# PX4mNode_V0_1_1.net
KiCad netlist of a schematic drawn in EAGLE
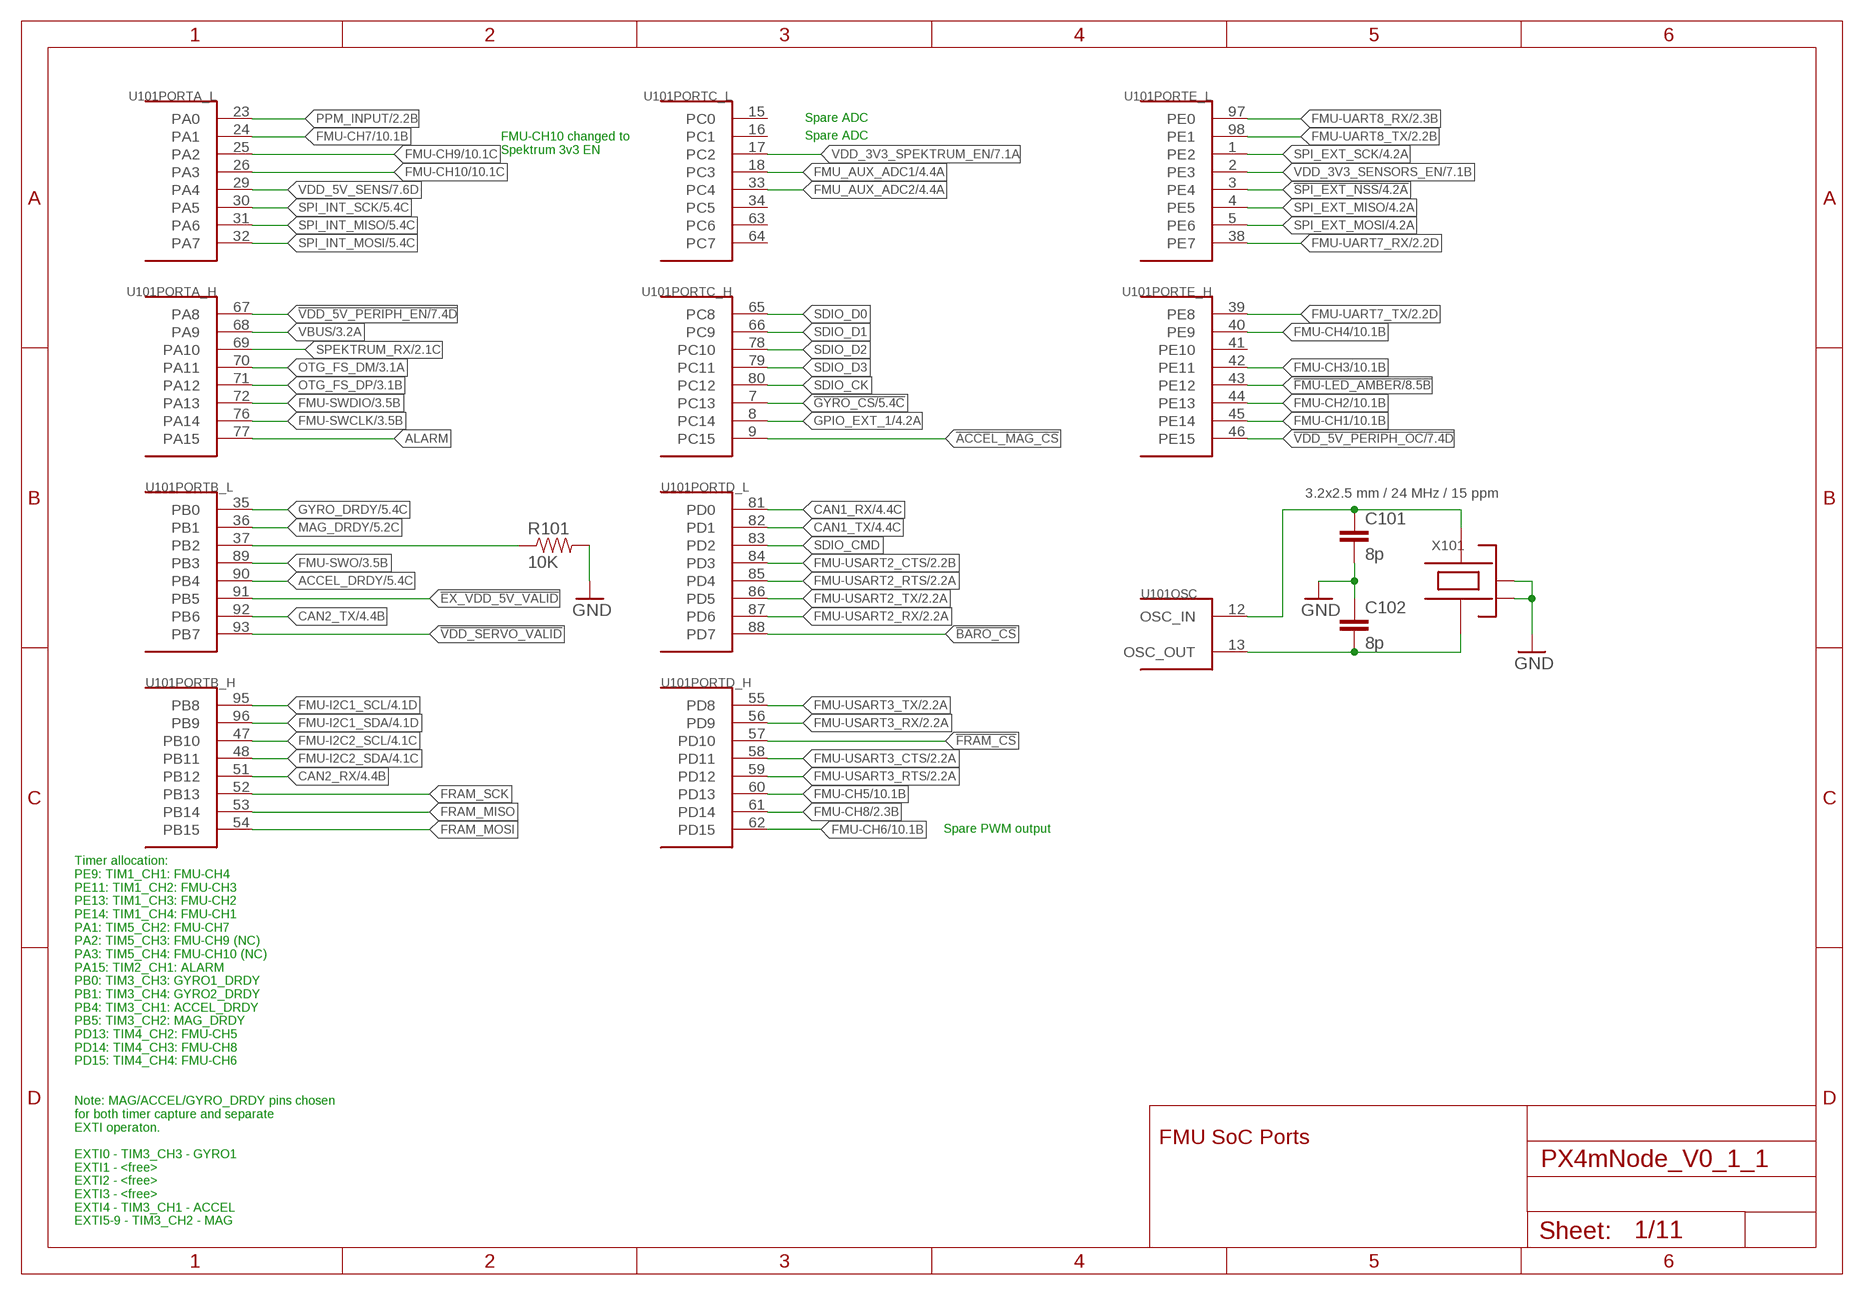
[diagram p0: schematic, sheet 1]
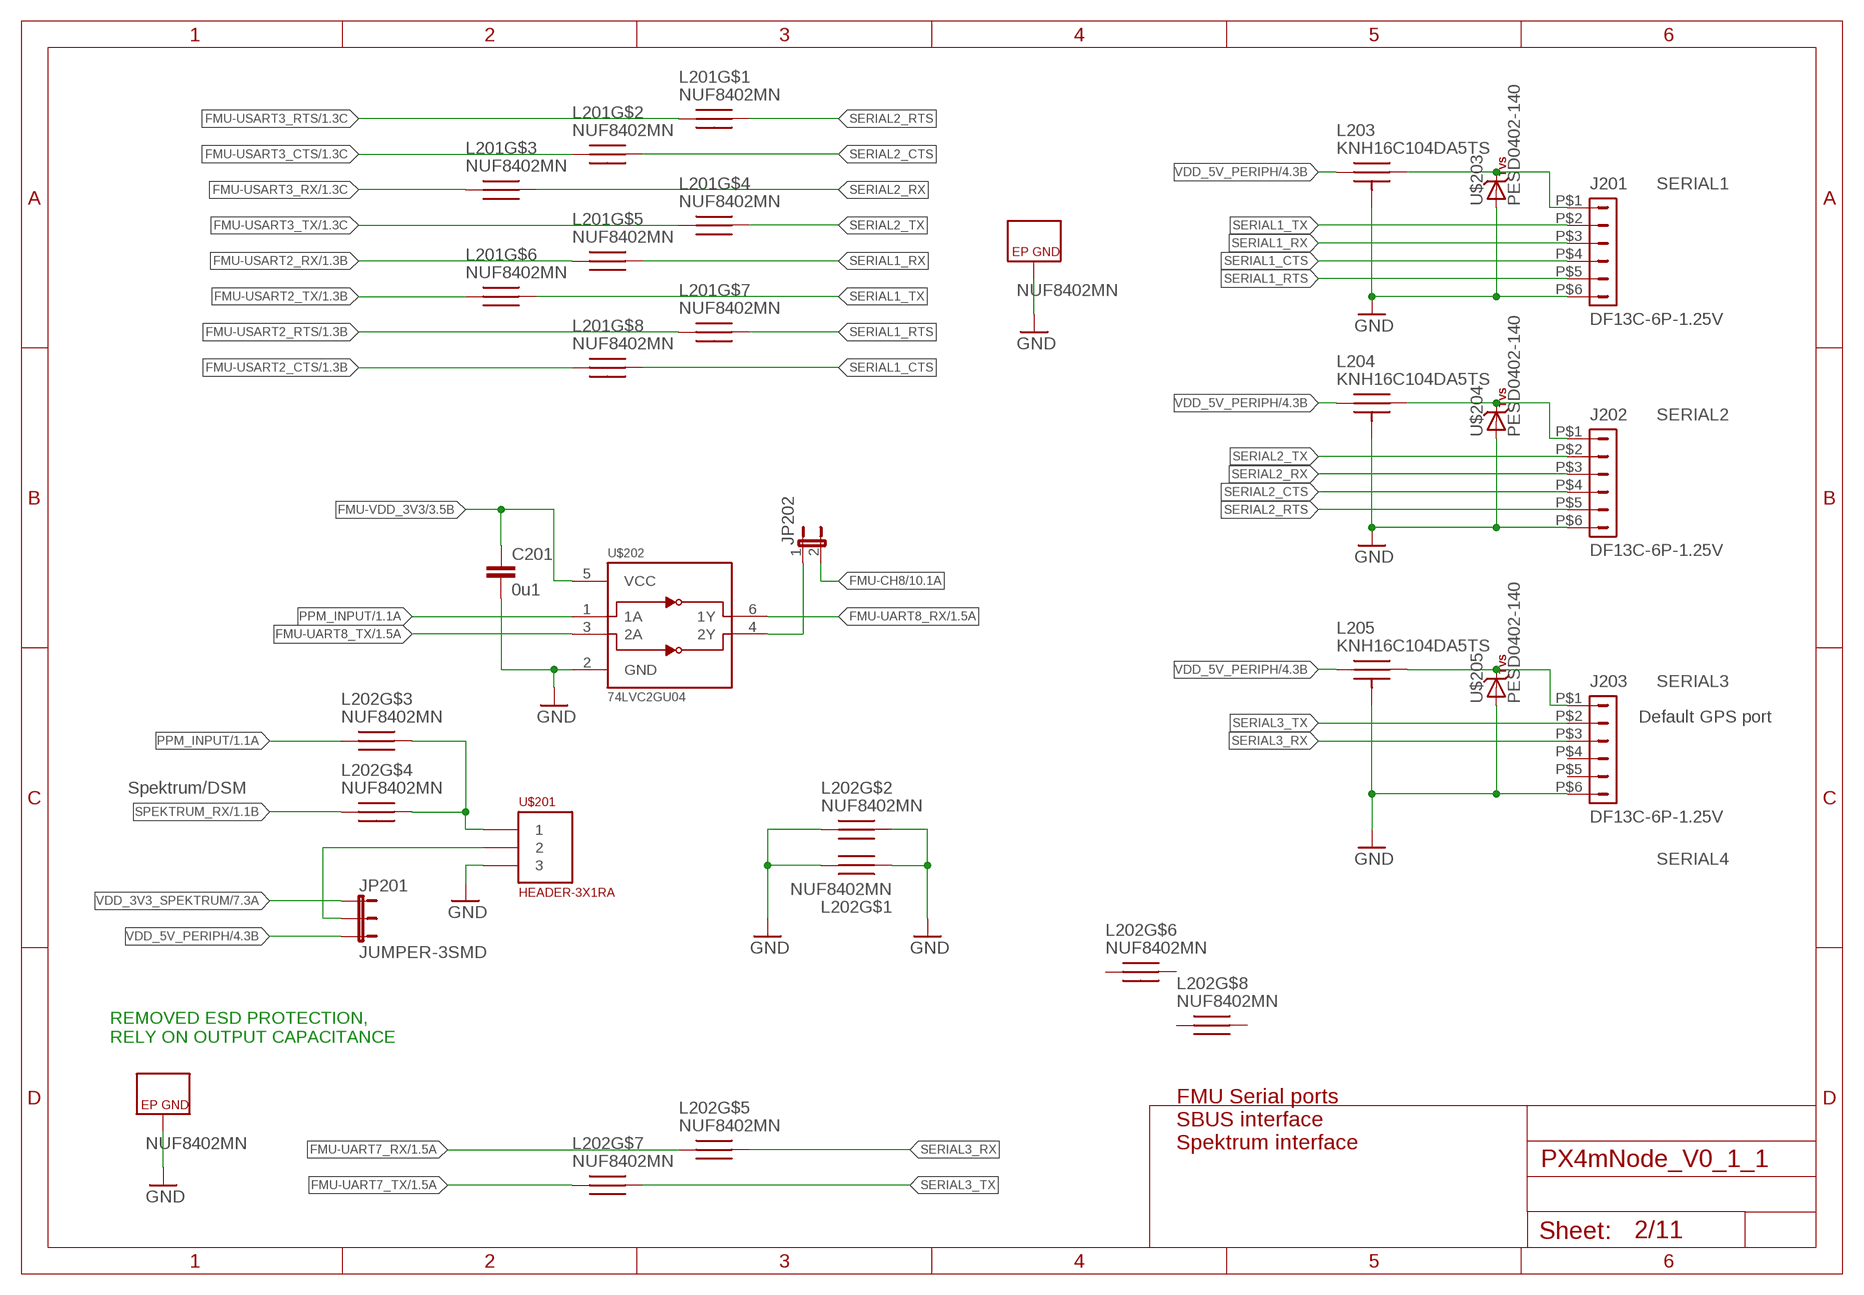
[diagram p1: schematic, sheet 2]
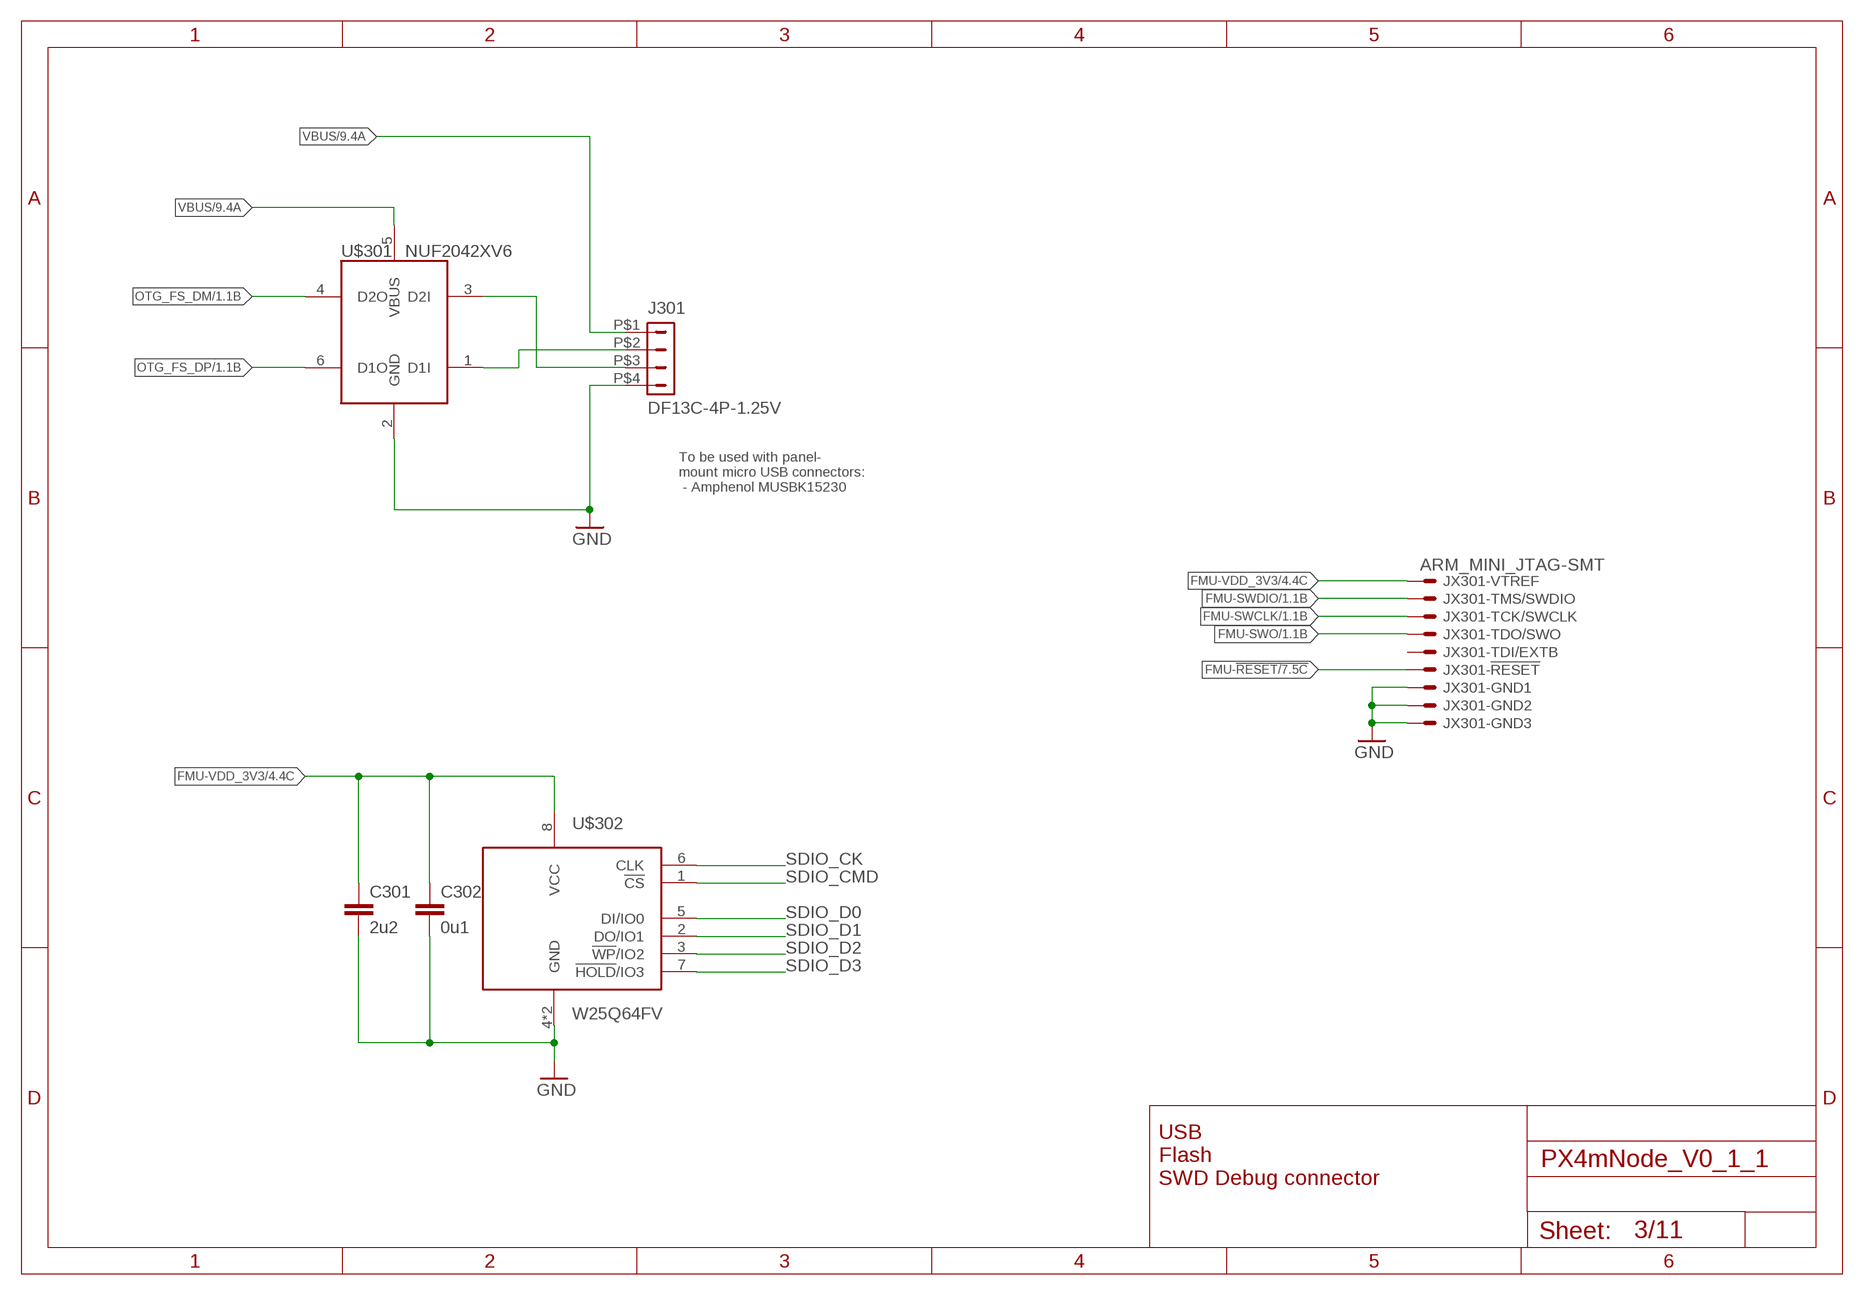
[diagram p2: schematic, sheet 3]
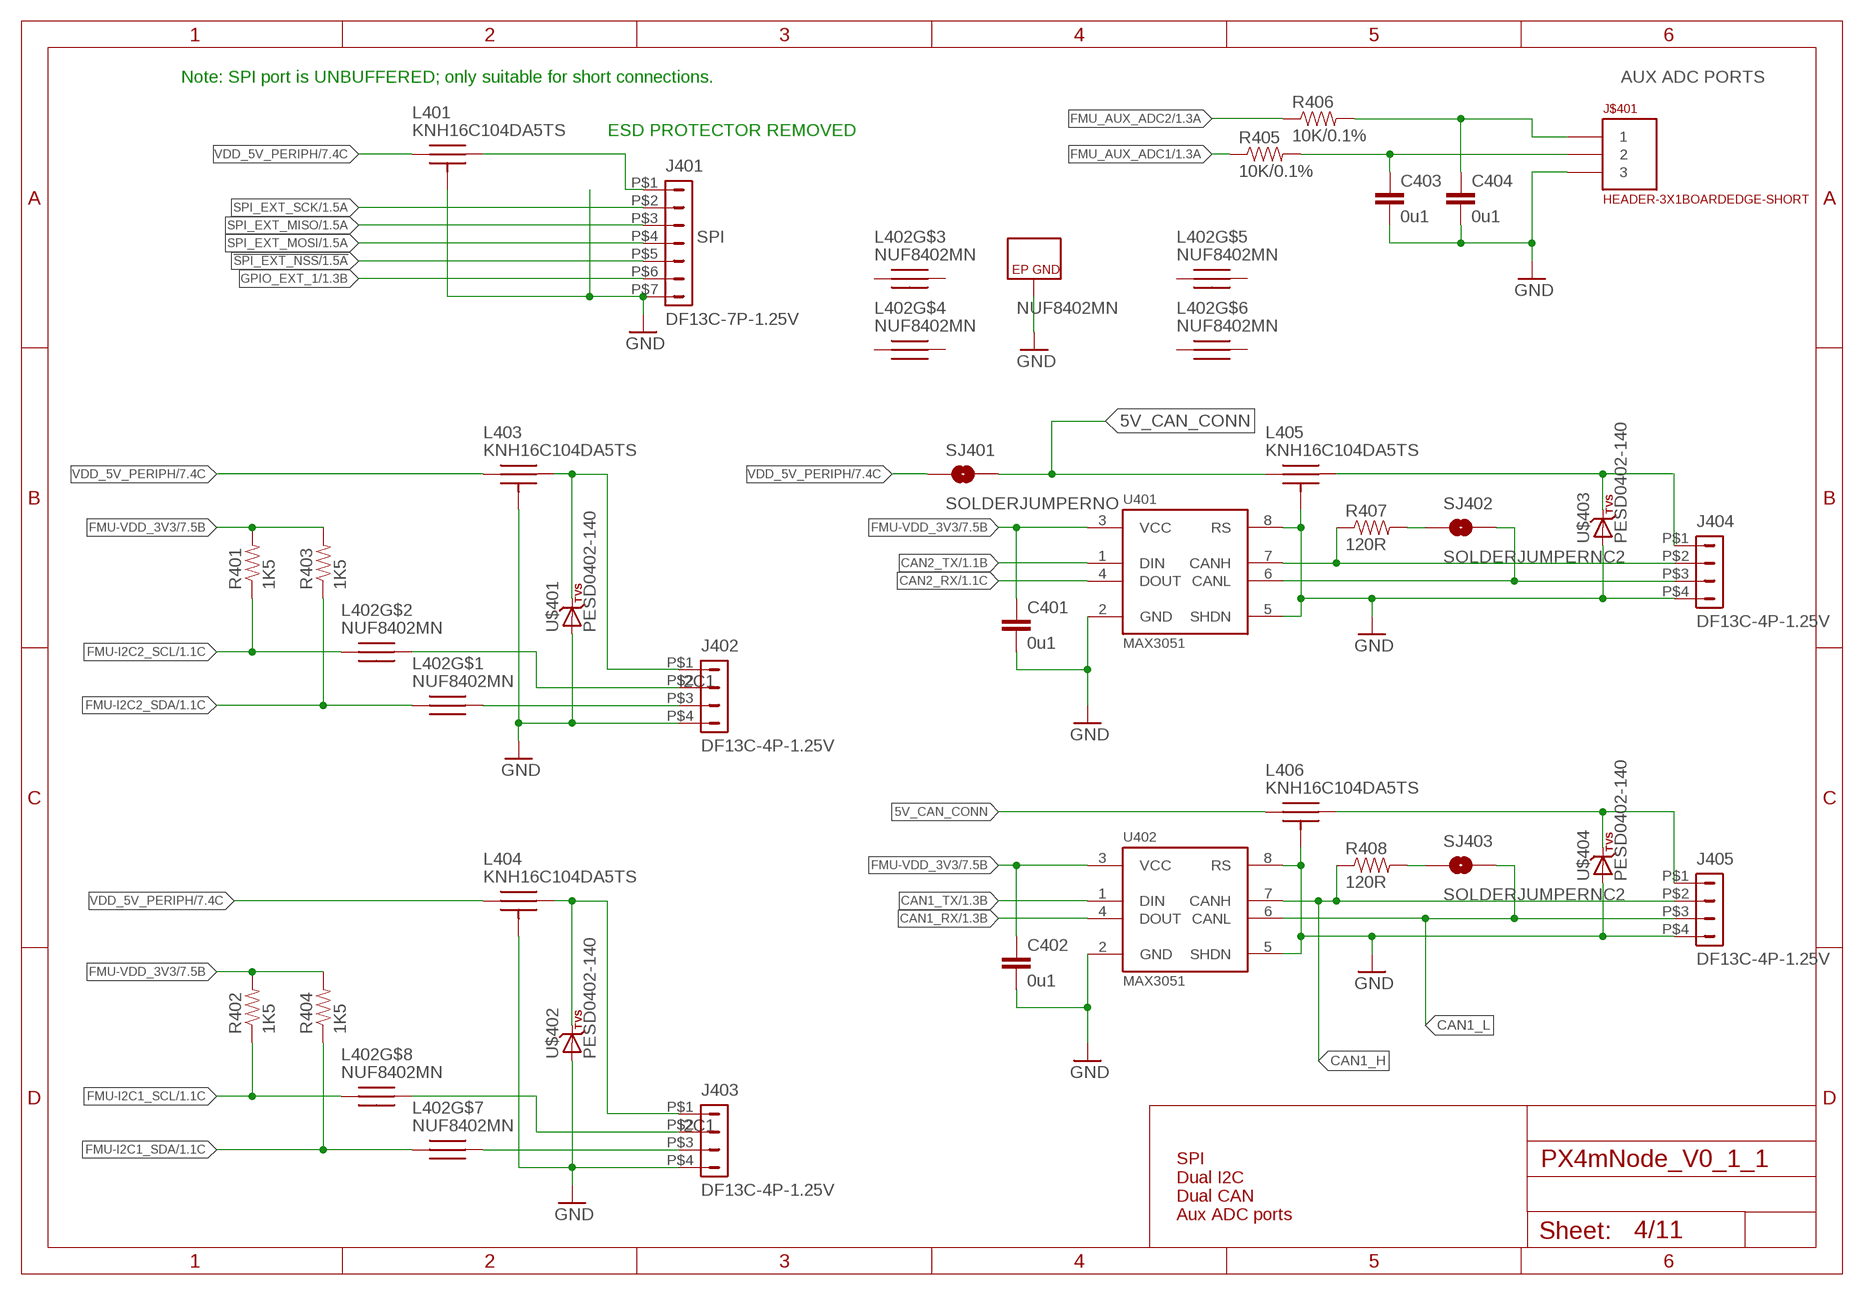
[diagram p3: schematic, sheet 4]
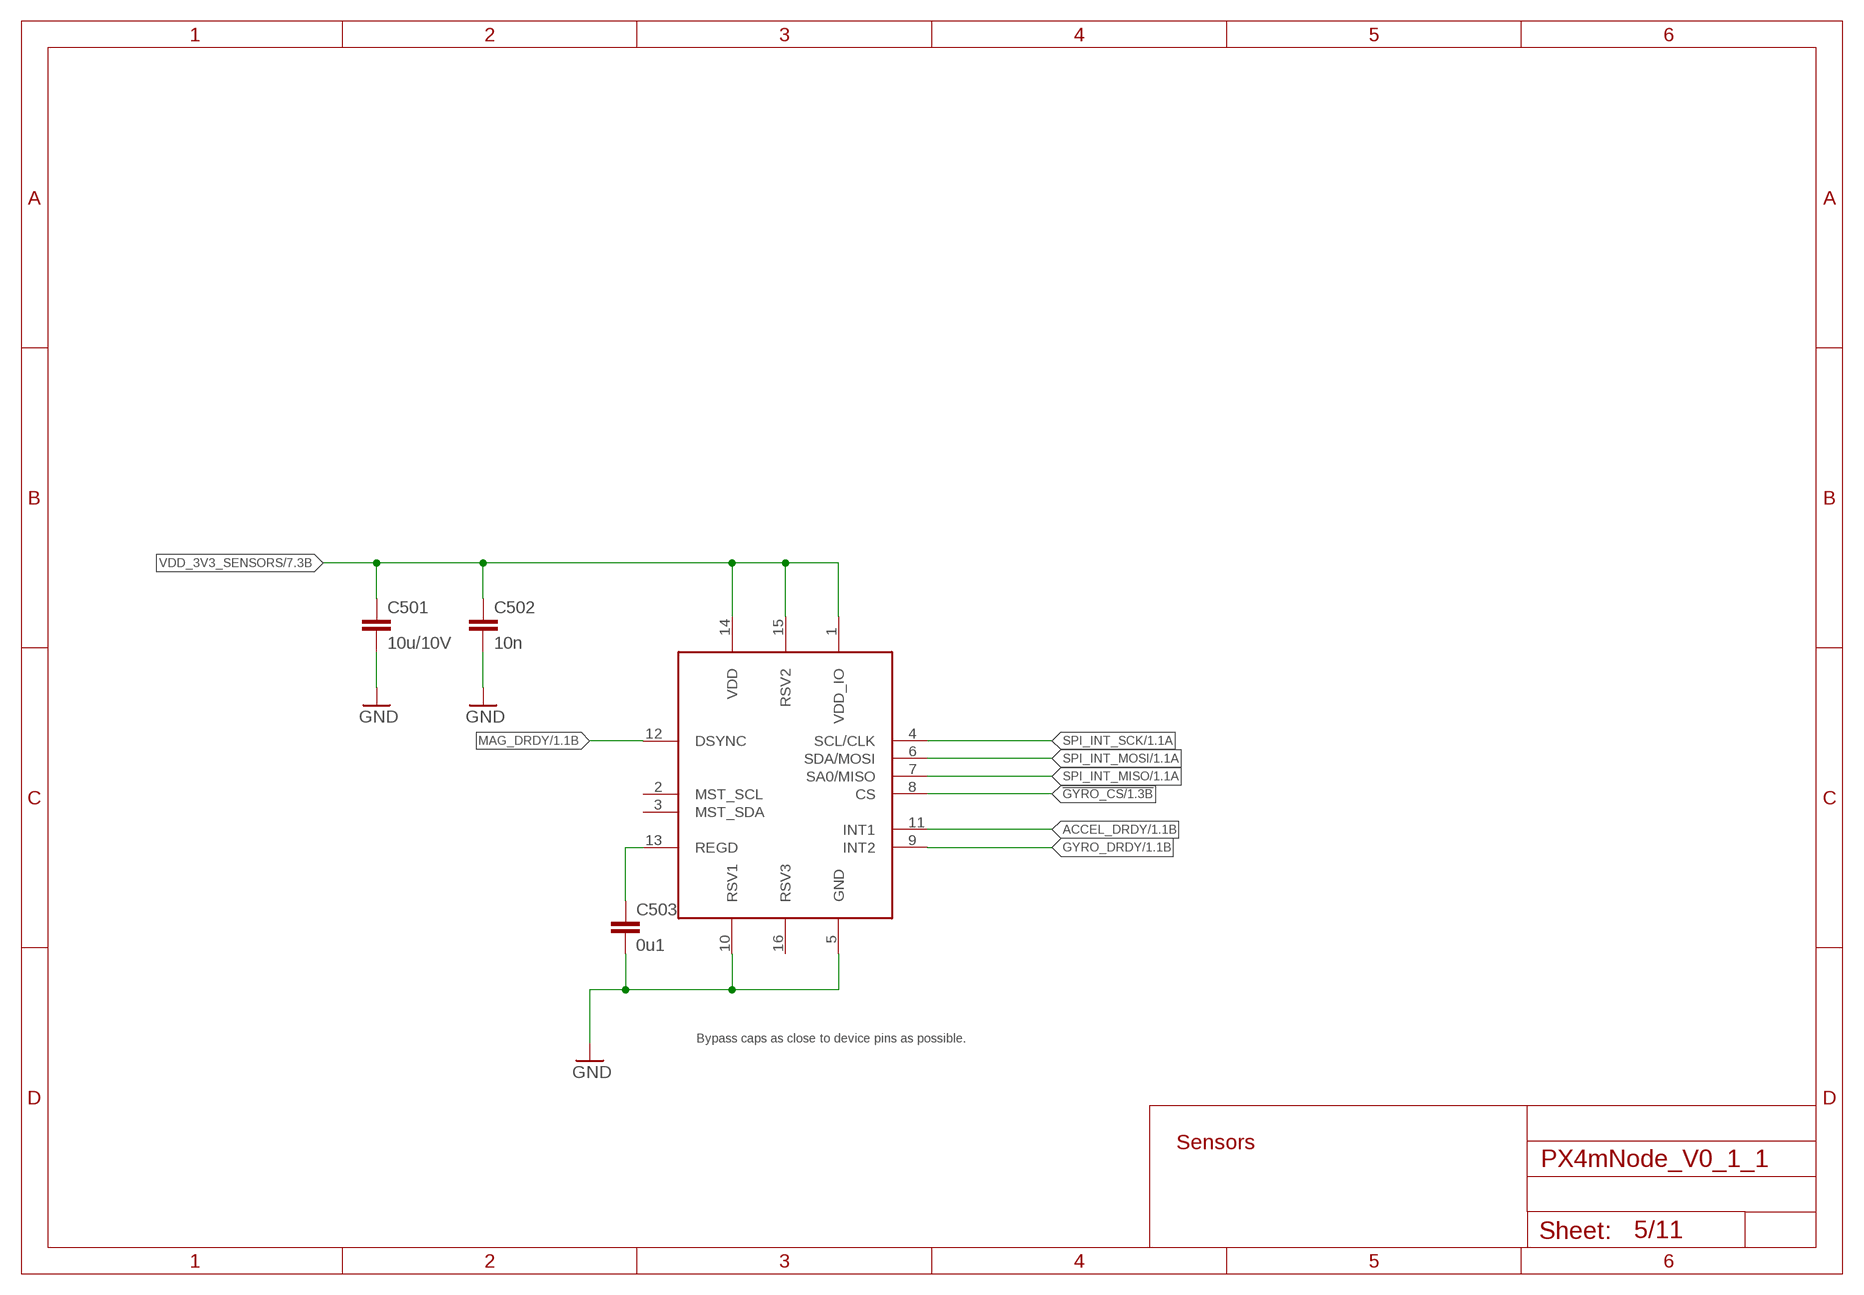
[diagram p4: schematic, sheet 5]
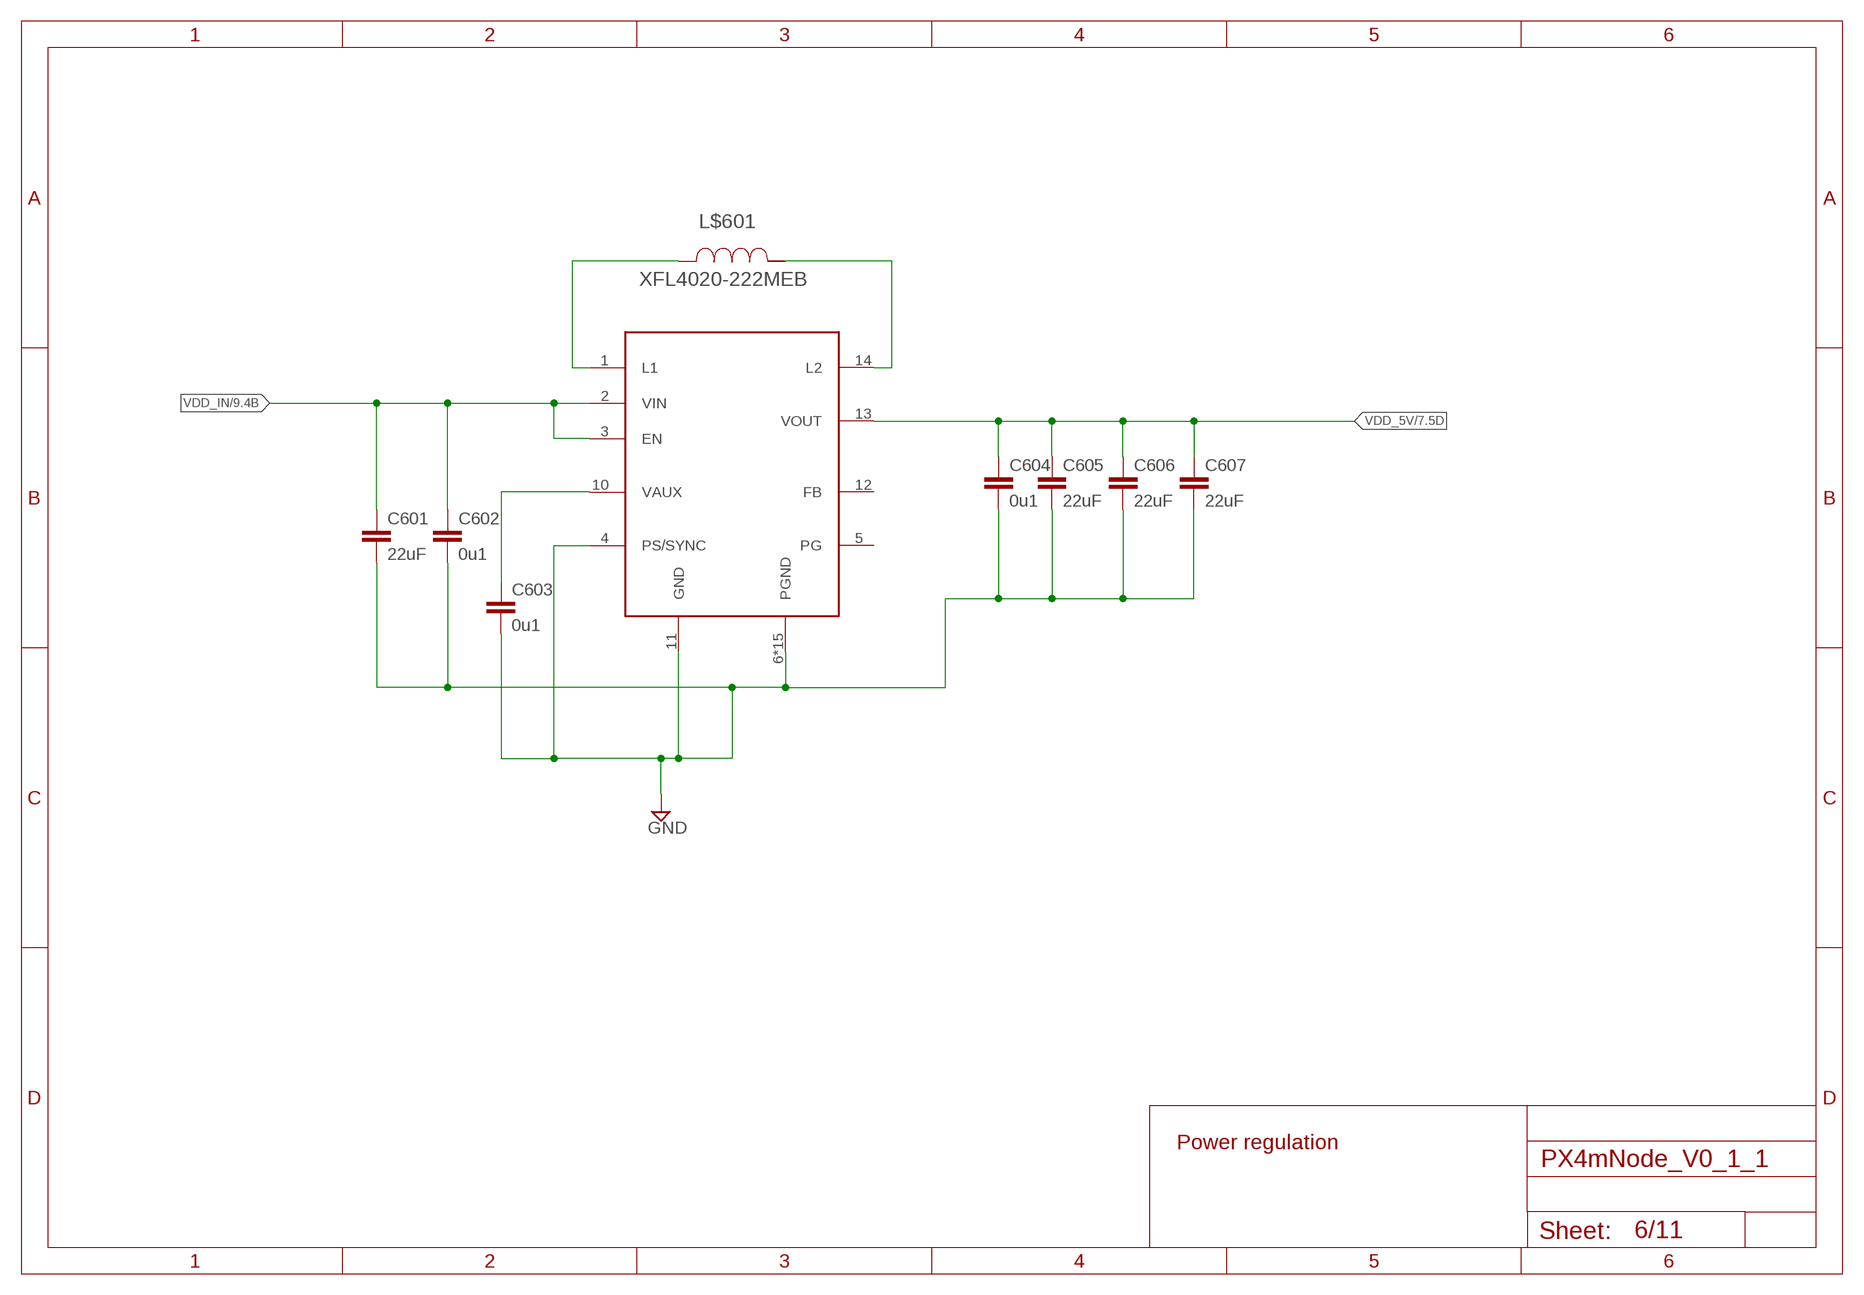
[diagram p5: schematic, sheet 6]
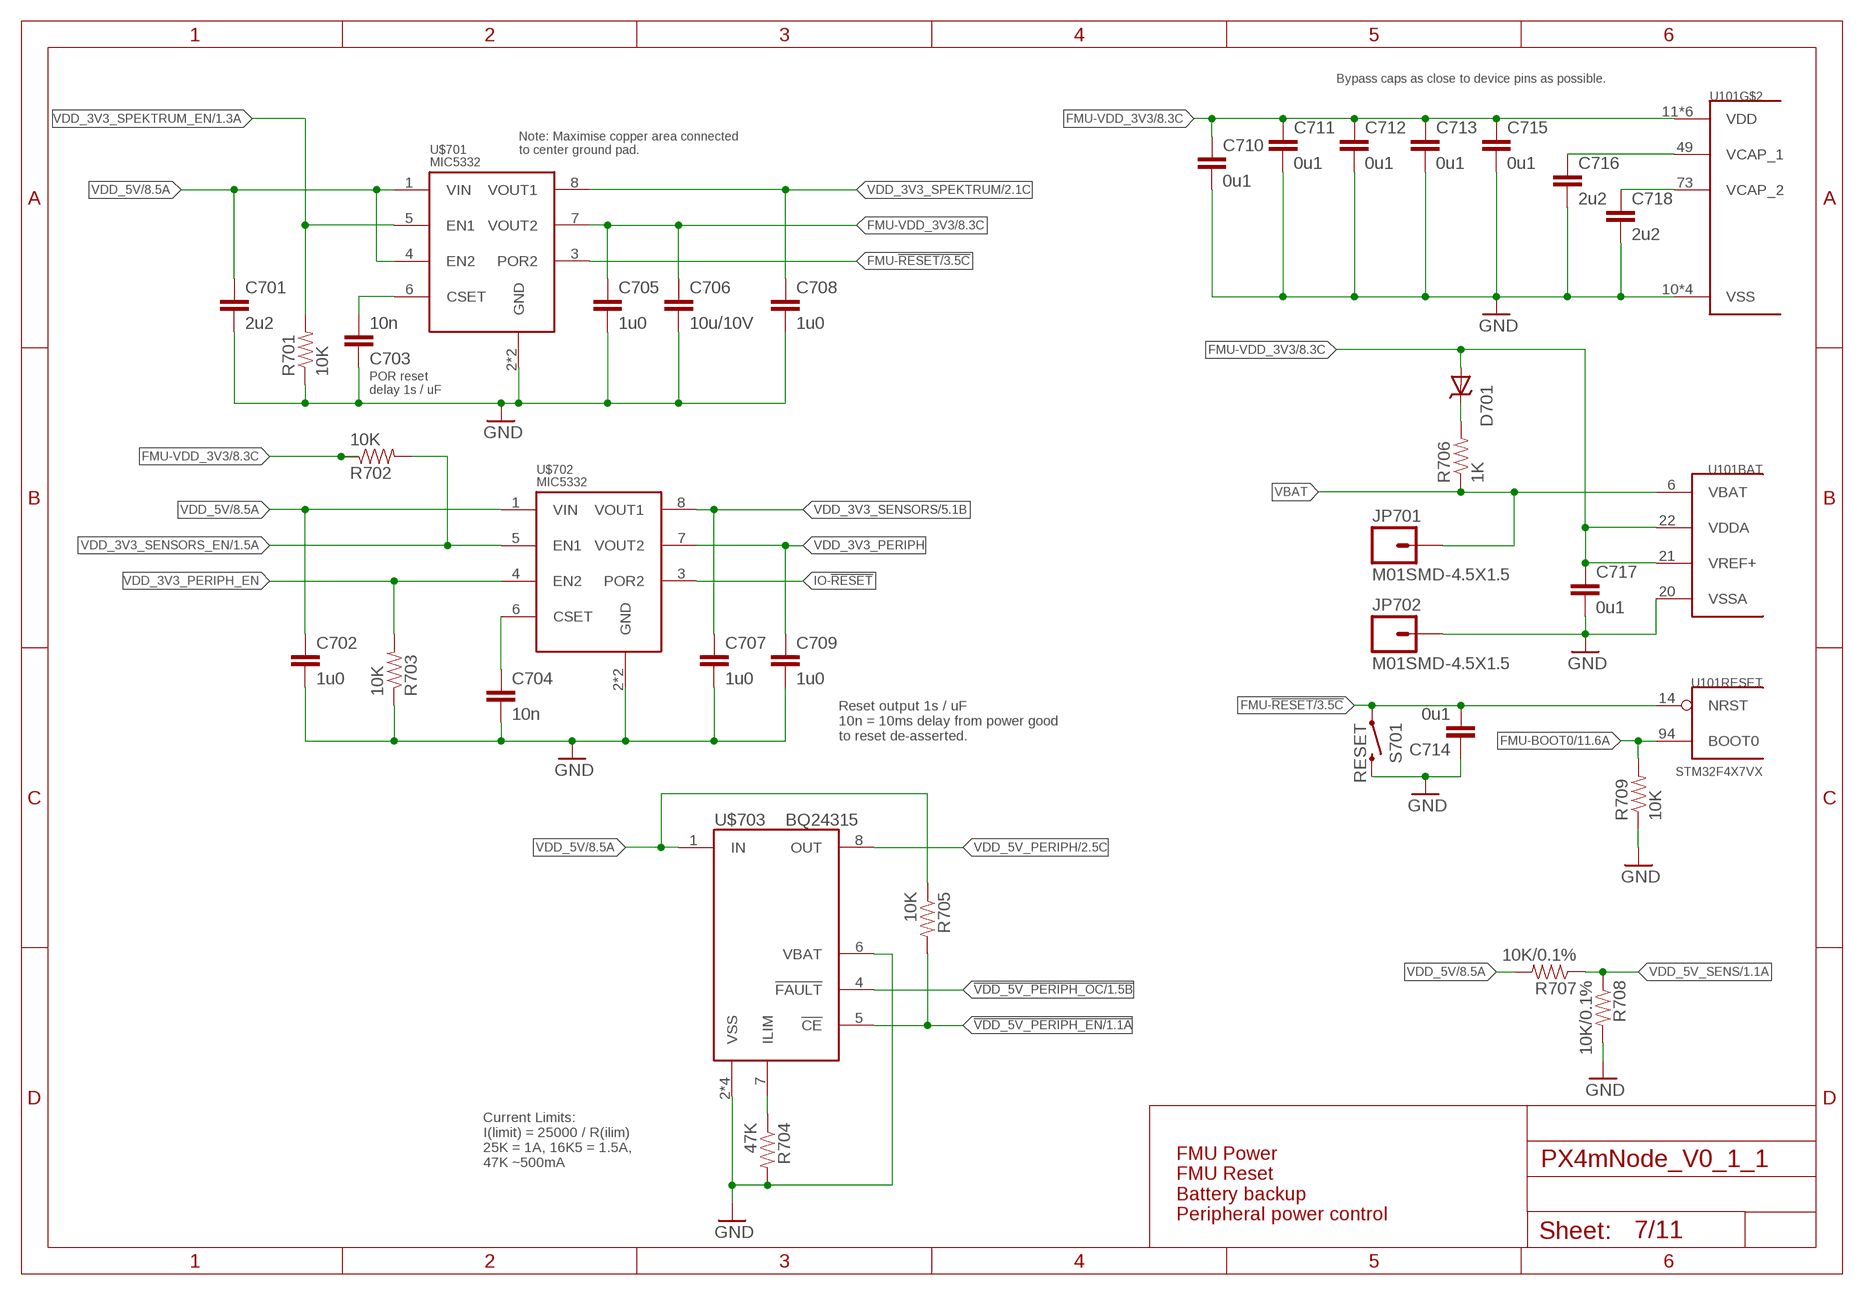
[diagram p6: schematic, sheet 7]
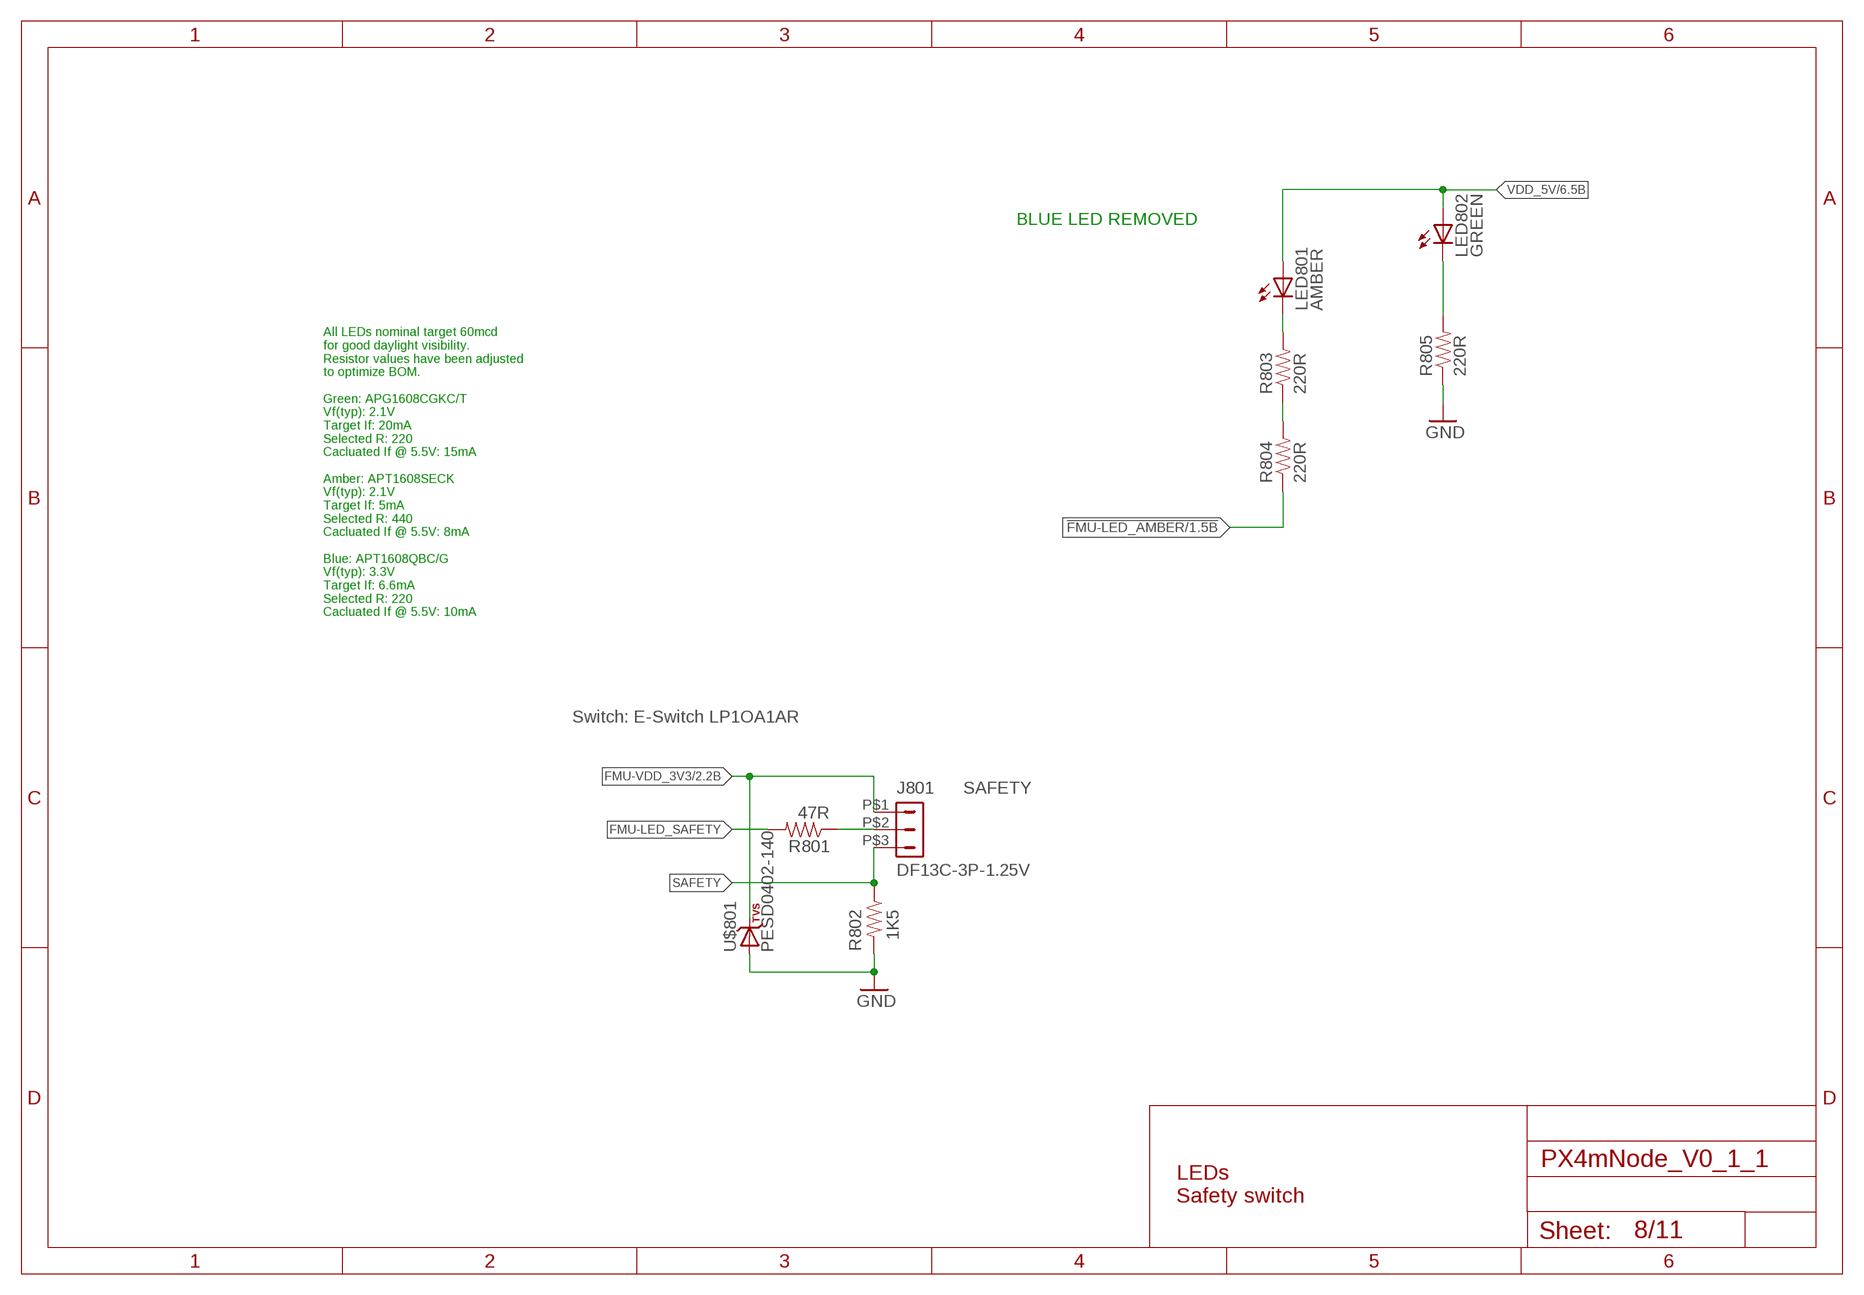
[diagram p7: schematic, sheet 8]
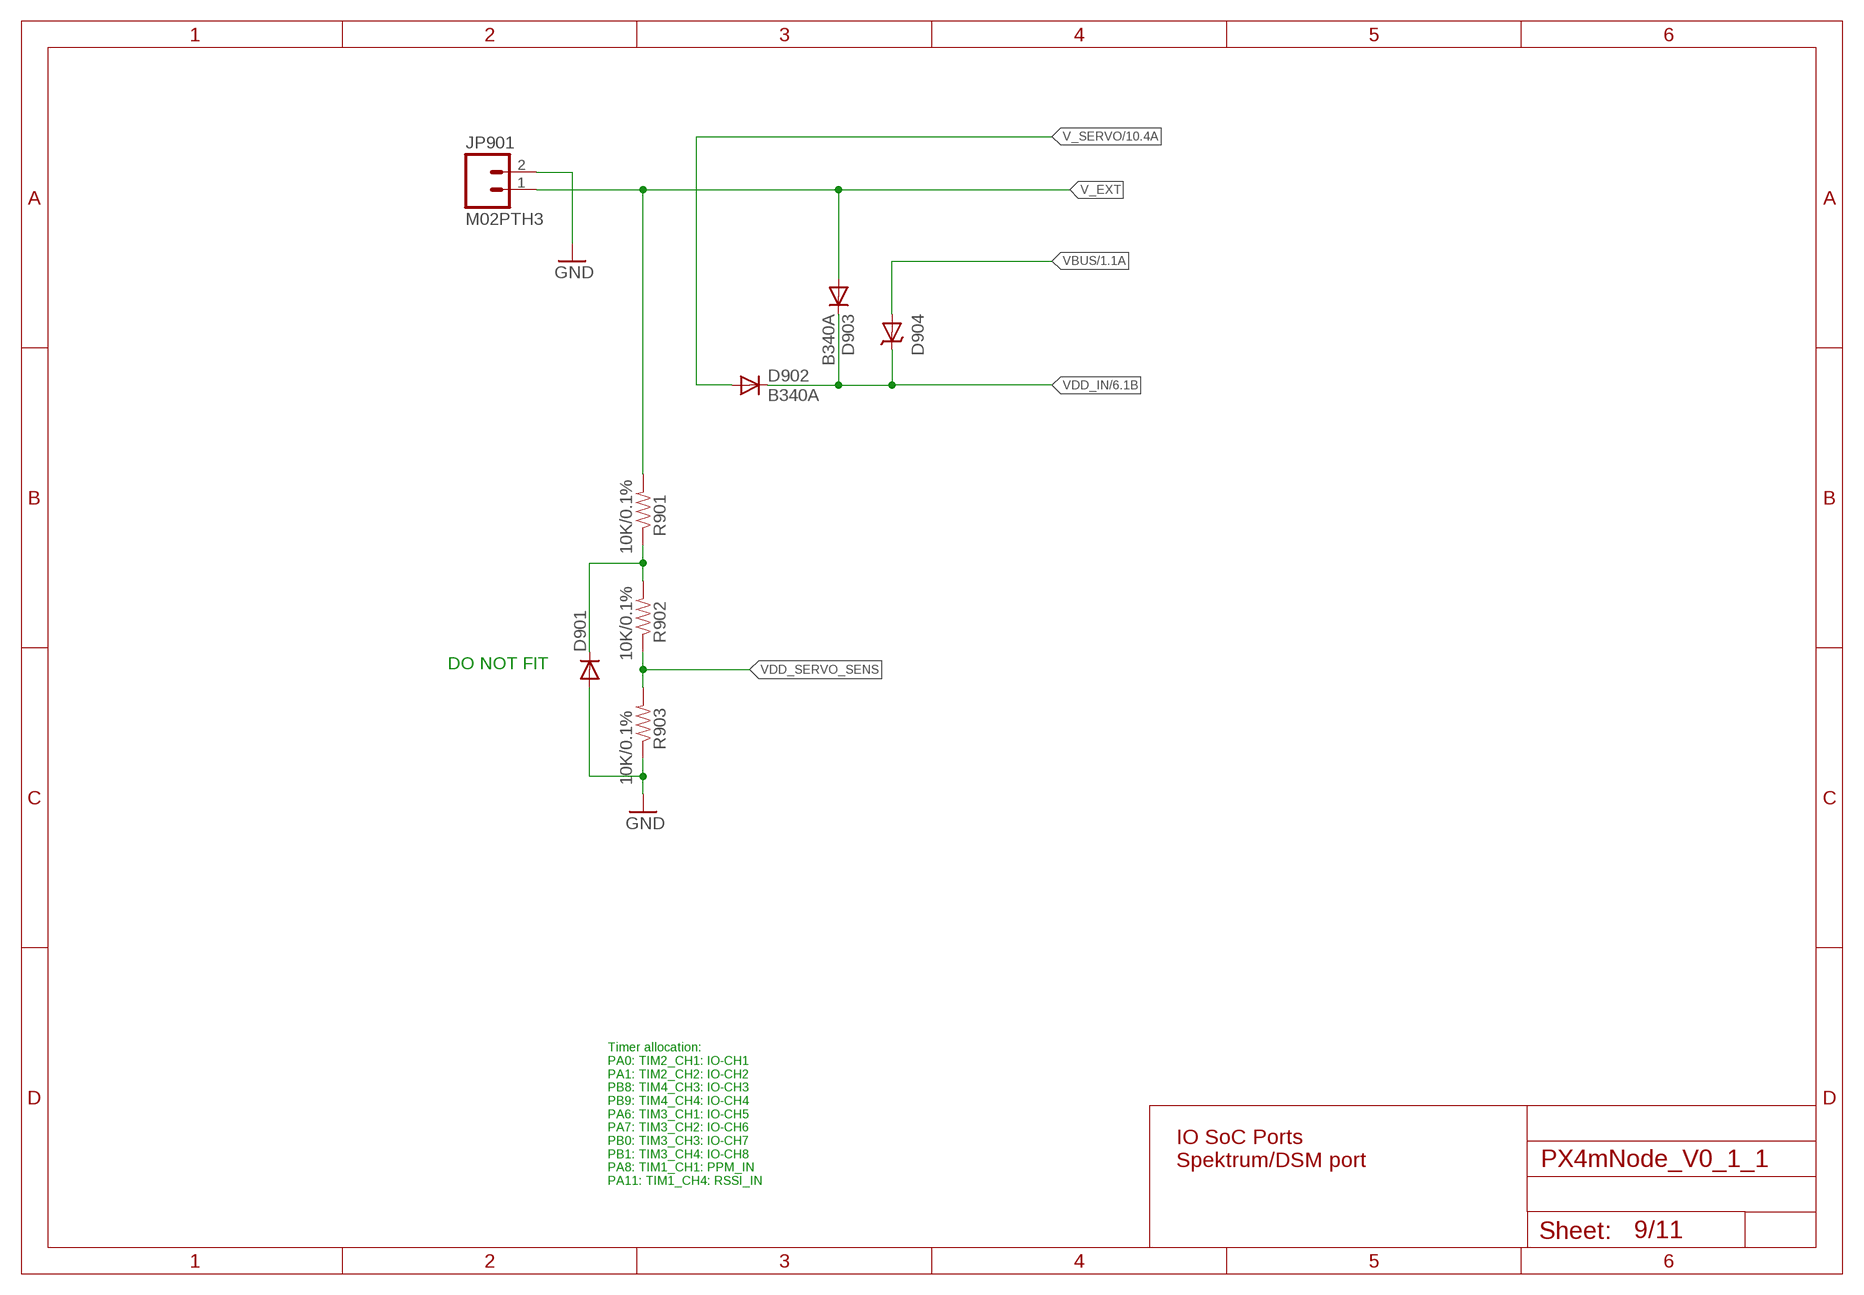
[diagram p8: schematic, sheet 9]
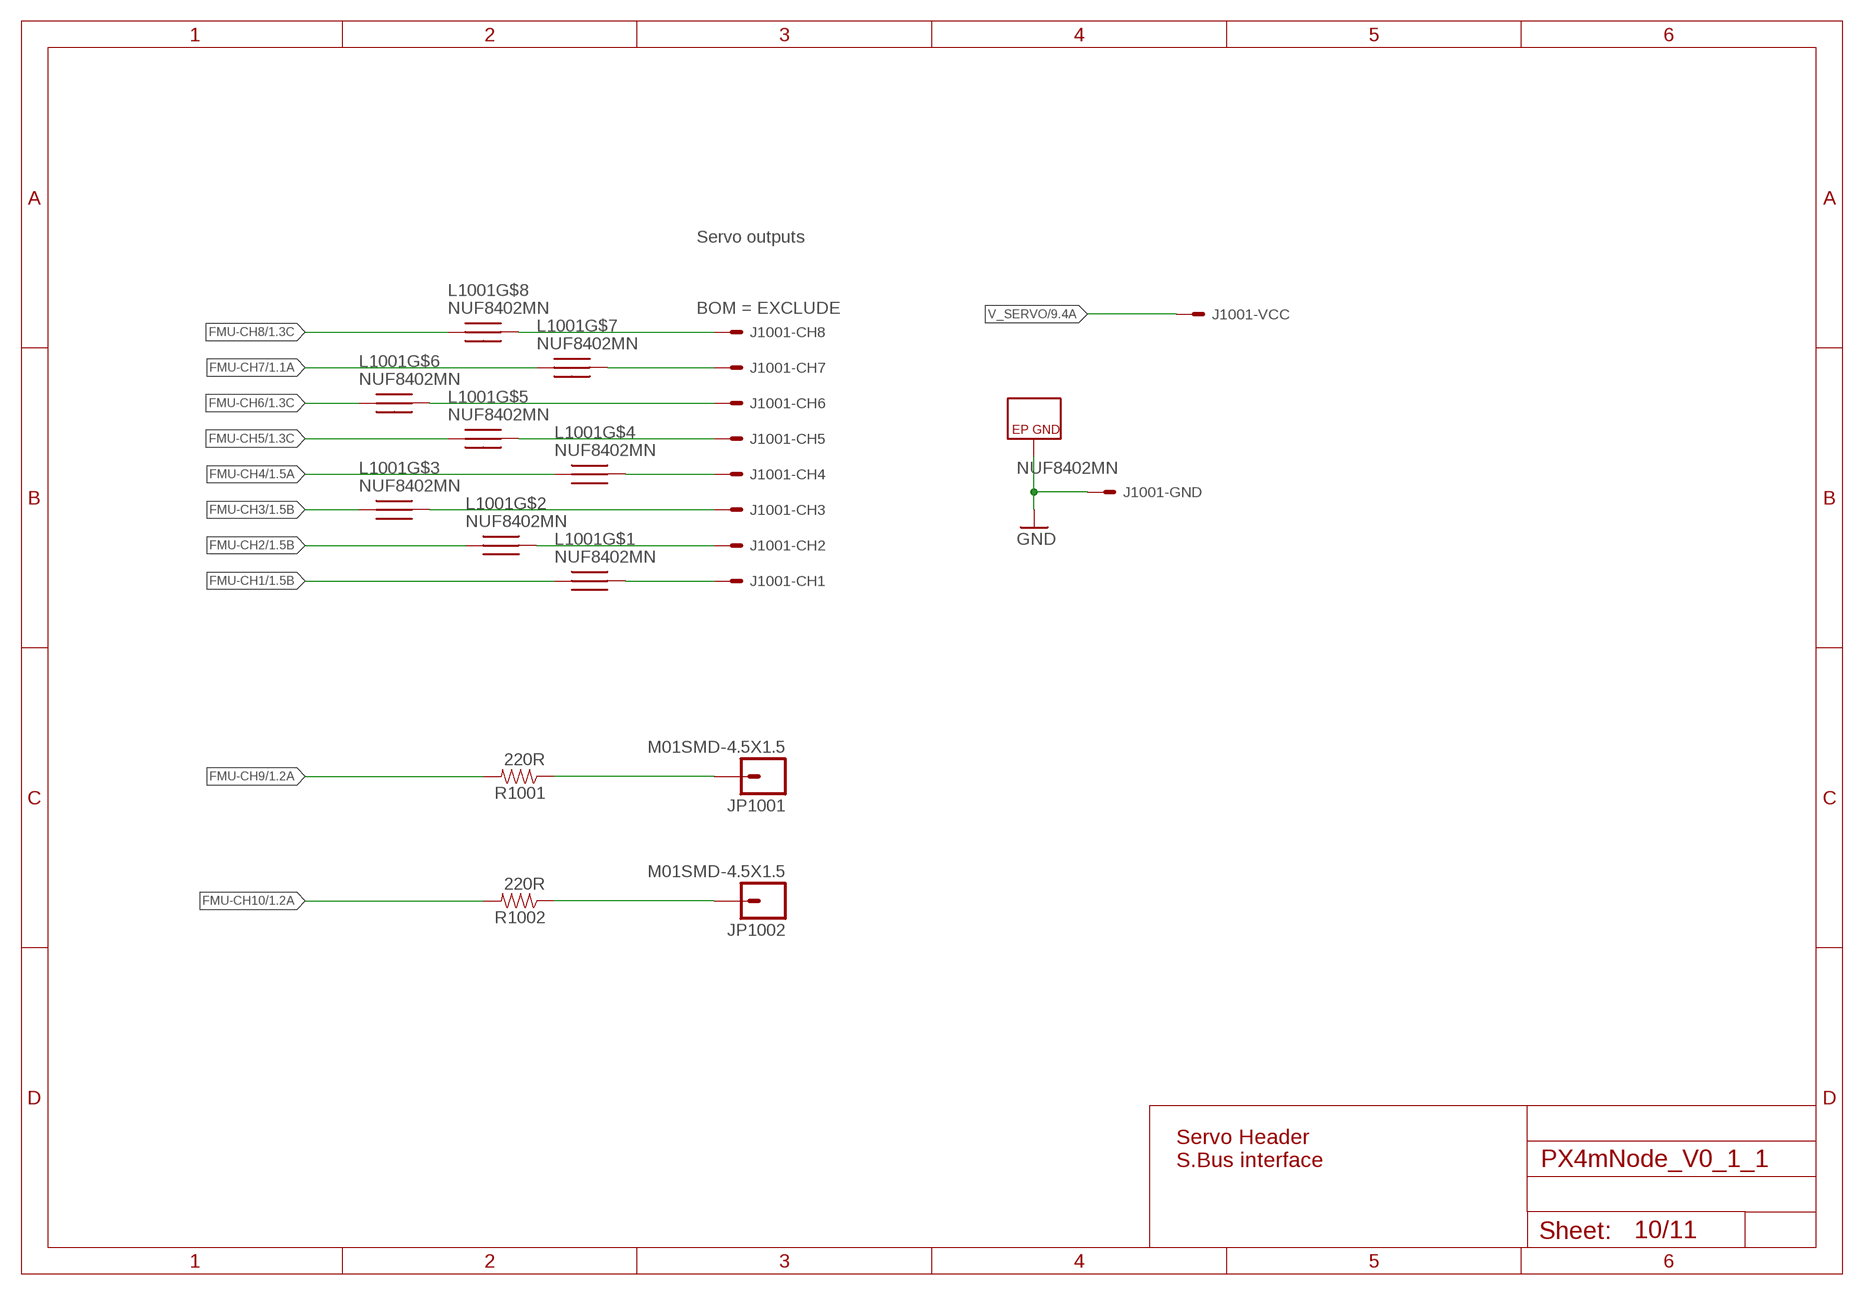
[diagram p9: schematic, sheet 10]
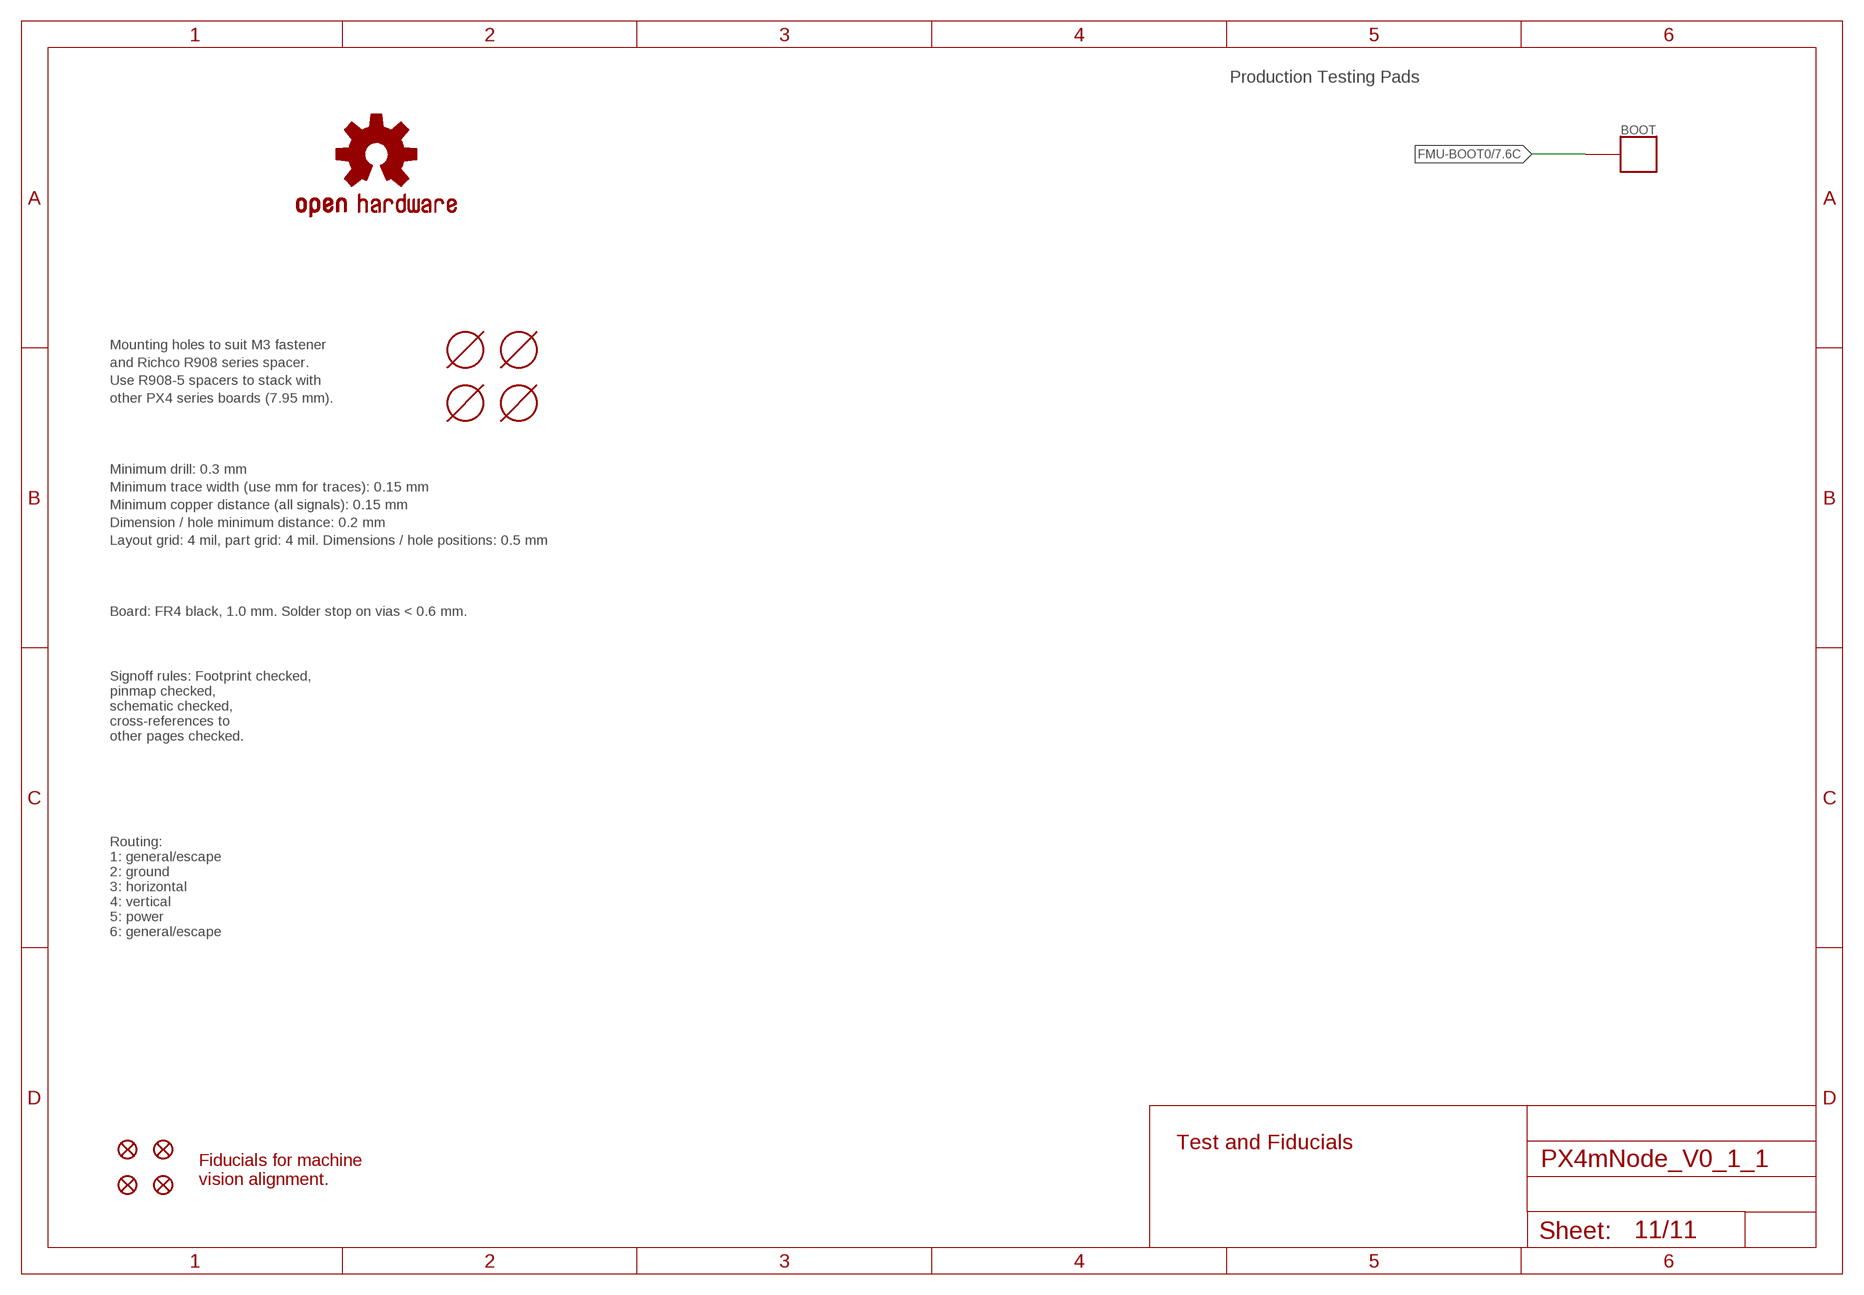
[diagram p10: schematic, sheet 11]

(export (version "E")
  (design (tool "Eeschema 10.0.6"))
  (components
    (comp (ref "C201")
      (value "0u1")
      (footprint "eagle-import:0402-CAP")
      (fields (field (name "PARTNO") "CC0402ZRY5V7BB104"))
      (libsource (lib "eagle-import") (part "CAP0402"))
    )
    (comp (ref "J201")
      (value "DF13C-6P-1.25V")
      (footprint "eagle-import:DF13C-6P-1.25V")
      (fields (field (name "PARTNO") "DF13C-6P-1.25V(20)"))
      (libsource (lib "eagle-import") (part "DF13-6P-1.25V"))
    )
    (comp (ref "J202")
      (value "DF13C-6P-1.25V")
      (footprint "eagle-import:DF13C-6P-1.25V")
      (fields (field (name "PARTNO") "DF13C-6P-1.25V(20)"))
      (libsource (lib "eagle-import") (part "DF13-6P-1.25V"))
    )
    (comp (ref "J203")
      (value "DF13C-6P-1.25V")
      (footprint "eagle-import:DF13C-6P-1.25V")
      (fields (field (name "PARTNO") "DF13C-6P-1.25V(20)"))
      (libsource (lib "eagle-import") (part "DF13-6P-1.25V"))
    )
    (comp (ref "JP201")
      (value "JUMPER-3SMD")
      (footprint "eagle-import:SJ_3")
      (libsource (lib "eagle-import") (part "JUMPER-3SMD"))
    )
    (comp (ref "JP202")
      (value "JUMPER-2SMD-NO")
      (footprint "eagle-import:SJ_2S-NO")
      (libsource (lib "eagle-import") (part "JUMPER-2SMD-NO"))
    )
    (comp (ref "L201")
      (value "NUF8402MN")
      (footprint "eagle-import:DFN16-THIN")
      (libsource (lib "eagle-import") (part "NUF8402MN"))
    )
    (comp (ref "L202")
      (value "NUF8402MN")
      (footprint "eagle-import:DFN16-THIN")
      (libsource (lib "eagle-import") (part "NUF8402MN"))
    )
    (comp (ref "L203")
      (value "KNH16C104DA5TS")
      (footprint "eagle-import:KYOCERA-KNH16-DA")
      (libsource (lib "eagle-import") (part "KNH16C104DA5TS"))
    )
    (comp (ref "L204")
      (value "KNH16C104DA5TS")
      (footprint "eagle-import:KYOCERA-KNH16-DA")
      (libsource (lib "eagle-import") (part "KNH16C104DA5TS"))
    )
    (comp (ref "L205")
      (value "KNH16C104DA5TS")
      (footprint "eagle-import:KYOCERA-KNH16-DA")
      (libsource (lib "eagle-import") (part "KNH16C104DA5TS"))
    )
    (comp (ref "U$201")
      (value "HEADER-3X1RA")
      (footprint "eagle-import:3X1RA")
      (libsource (lib "eagle-import") (part "HEADER-3X1RA"))
    )
    (comp (ref "U$202")
      (value "74LVC2GU04")
      (footprint "eagle-import:SOT363_PHILIPS")
      (libsource (lib "eagle-import") (part "74LVC2GU04"))
    )
    (comp (ref "U$203")
      (value "PESD0402-140")
      (footprint "eagle-import:0402-TVS")
      (libsource (lib "eagle-import") (part "DIODE-TVS"))
    )
    (comp (ref "U$204")
      (value "PESD0402-140")
      (footprint "eagle-import:0402-TVS")
      (libsource (lib "eagle-import") (part "DIODE-TVS"))
    )
    (comp (ref "U$205")
      (value "PESD0402-140")
      (footprint "eagle-import:0402-TVS")
      (libsource (lib "eagle-import") (part "DIODE-TVS"))
    )
    (comp (ref "C501")
      (value "10u/10V")
      (footprint "eagle-import:0805-CAP")
      (fields (field (name "PARTNO") "CC0805ZKY5V6BB106"))
      (libsource (lib "eagle-import") (part "CAP0805"))
    )
    (comp (ref "C502")
      (value "10n")
      (footprint "eagle-import:0402-CAP")
      (fields (field (name "PARTNO") "CC0402KRX7R7BB103"))
      (libsource (lib "eagle-import") (part "CAP0402"))
    )
    (comp (ref "C503")
      (value "0u1")
      (footprint "eagle-import:0402-CAP")
      (fields (field (name "PARTNO") "CC0402ZRY5V7BB104"))
      (libsource (lib "eagle-import") (part "CAP0402"))
    )
    (comp (ref "U$501")
      (value "MAX21100")
      (footprint "eagle-import:16LGA-3X3")
      (libsource (lib "eagle-import") (part "MAX21100"))
    )
    (comp (ref "C101")
      (value "8p")
      (footprint "eagle-import:0402-CAP")
      (fields (field (name "PARTNO") "C1005C0G1H080C"))
      (libsource (lib "eagle-import") (part "CAP0402"))
    )
    (comp (ref "C102")
      (value "8p")
      (footprint "eagle-import:0402-CAP")
      (fields (field (name "PARTNO") "C1005C0G1H080C"))
      (libsource (lib "eagle-import") (part "CAP0402"))
    )
    (comp (ref "R101")
      (value "10K")
      (footprint "eagle-import:0402-RES")
      (fields (field (name "PARTNO") "RC0402FR-0710KL"))
      (libsource (lib "eagle-import") (part "RESISTOR0402-RES"))
    )
    (comp (ref "U101")
      (value "STM32F4X7VX")
      (footprint "eagle-import:TQFP100")
      (fields (field (name "PARTNO") "STM32F427VI"))
      (libsource (lib "eagle-import") (part "STM32F4X7VX"))
    )
    (comp (ref "X101")
      (value "3.2x2.5 mm / 24 MHz / 15 ppm")
      (footprint "eagle-import:OSCILLATOR-3.2X2.5")
      (fields (field (name "PARTNO") "NX3225SA-24.000000MHZ"))
      (libsource (lib "eagle-import") (part "OSCILLATOR-3.2X2.5"))
    )
    (comp (ref "C401")
      (value "0u1")
      (footprint "eagle-import:0402-CAP")
      (fields (field (name "PARTNO") "CC0402ZRY5V7BB104"))
      (libsource (lib "eagle-import") (part "CAP0402"))
    )
    (comp (ref "C402")
      (value "0u1")
      (footprint "eagle-import:0402-CAP")
      (fields (field (name "PARTNO") "CC0402ZRY5V7BB104"))
      (libsource (lib "eagle-import") (part "CAP0402"))
    )
    (comp (ref "C403")
      (value "0u1")
      (footprint "eagle-import:0402-CAP")
      (fields (field (name "PARTNO") "CC0402ZRY5V7BB104"))
      (libsource (lib "eagle-import") (part "CAP0402"))
    )
    (comp (ref "C404")
      (value "0u1")
      (footprint "eagle-import:0402-CAP")
      (fields (field (name "PARTNO") "CC0402ZRY5V7BB104"))
      (libsource (lib "eagle-import") (part "CAP0402"))
    )
    (comp (ref "J$401")
      (value "HEADER-3X1BOARDEDGE-SHORT")
      (footprint "eagle-import:HEADER_3X01_SMD_H_BOARD_EDGE_SHORT")
      (libsource (lib "eagle-import") (part "HEADER-3X1BOARDEDGE-SHORT"))
    )
    (comp (ref "J401")
      (value "DF13C-7P-1.25V")
      (footprint "eagle-import:DF13C-7P-1.25V")
      (fields (field (name "PARTNO") "DF13C-7P-1.25V(20)"))
      (libsource (lib "eagle-import") (part "DF13-7P-1.25V"))
    )
    (comp (ref "J402")
      (value "DF13C-4P-1.25V")
      (footprint "eagle-import:DF13C-4P-1.25V")
      (fields (field (name "PARTNO") "DF13C-4P-1.25V(20)"))
      (libsource (lib "eagle-import") (part "DF13-4P-1.25V"))
    )
    (comp (ref "J403")
      (value "DF13C-4P-1.25V")
      (footprint "eagle-import:DF13C-4P-1.25V")
      (fields (field (name "PARTNO") "DF13C-4P-1.25V(20)"))
      (libsource (lib "eagle-import") (part "DF13-4P-1.25V"))
    )
    (comp (ref "J404")
      (value "DF13C-4P-1.25V")
      (footprint "eagle-import:DF13C-4P-1.25V")
      (fields (field (name "PARTNO") "DF13C-4P-1.25V(20)"))
      (libsource (lib "eagle-import") (part "DF13-4P-1.25V"))
    )
    (comp (ref "J405")
      (value "DF13C-4P-1.25V")
      (footprint "eagle-import:DF13C-4P-1.25V")
      (fields (field (name "PARTNO") "DF13C-4P-1.25V(20)"))
      (libsource (lib "eagle-import") (part "DF13-4P-1.25V"))
    )
    (comp (ref "L401")
      (value "KNH16C104DA5TS")
      (footprint "eagle-import:KYOCERA-KNH16-DA")
      (libsource (lib "eagle-import") (part "KNH16C104DA5TS"))
    )
    (comp (ref "L402")
      (value "NUF8402MN")
      (footprint "eagle-import:DFN16-THIN")
      (libsource (lib "eagle-import") (part "NUF8402MN"))
    )
    (comp (ref "L403")
      (value "KNH16C104DA5TS")
      (footprint "eagle-import:KYOCERA-KNH16-DA")
      (libsource (lib "eagle-import") (part "KNH16C104DA5TS"))
    )
    (comp (ref "L404")
      (value "KNH16C104DA5TS")
      (footprint "eagle-import:KYOCERA-KNH16-DA")
      (libsource (lib "eagle-import") (part "KNH16C104DA5TS"))
    )
    (comp (ref "L405")
      (value "KNH16C104DA5TS")
      (footprint "eagle-import:KYOCERA-KNH16-DA")
      (libsource (lib "eagle-import") (part "KNH16C104DA5TS"))
    )
    (comp (ref "L406")
      (value "KNH16C104DA5TS")
      (footprint "eagle-import:KYOCERA-KNH16-DA")
      (libsource (lib "eagle-import") (part "KNH16C104DA5TS"))
    )
    (comp (ref "R401")
      (value "1K5")
      (footprint "eagle-import:0402-RES")
      (fields (field (name "PARTNO") "RC0402FR-071K5L"))
      (libsource (lib "eagle-import") (part "RESISTOR0402-RES"))
    )
    (comp (ref "R402")
      (value "1K5")
      (footprint "eagle-import:0402-RES")
      (fields (field (name "PARTNO") "RC0402FR-071K5L"))
      (libsource (lib "eagle-import") (part "RESISTOR0402-RES"))
    )
    (comp (ref "R403")
      (value "1K5")
      (footprint "eagle-import:0402-RES")
      (fields (field (name "PARTNO") "RC0402FR-071K5L"))
      (libsource (lib "eagle-import") (part "RESISTOR0402-RES"))
    )
    (comp (ref "R404")
      (value "1K5")
      (footprint "eagle-import:0402-RES")
      (fields (field (name "PARTNO") "RC0402FR-071K5L"))
      (libsource (lib "eagle-import") (part "RESISTOR0402-RES"))
    )
    (comp (ref "R405")
      (value "10K/0.1%")
      (footprint "eagle-import:0402-RES")
      (fields (field (name "PARTNO") "ERA-2AEB103X"))
      (libsource (lib "eagle-import") (part "RESISTOR0402-RES"))
    )
    (comp (ref "R406")
      (value "10K/0.1%")
      (footprint "eagle-import:0402-RES")
      (fields (field (name "PARTNO") "ERA-2AEB103X"))
      (libsource (lib "eagle-import") (part "RESISTOR0402-RES"))
    )
    (comp (ref "R407")
      (value "120R")
      (footprint "eagle-import:0402-RES")
      (fields (field (name "PARTNO") "RC0402FR-07120RL"))
      (libsource (lib "eagle-import") (part "RESISTOR0402-RES"))
    )
    (comp (ref "R408")
      (value "120R")
      (footprint "eagle-import:0402-RES")
      (fields (field (name "PARTNO") "RC0402FR-07120RL"))
      (libsource (lib "eagle-import") (part "RESISTOR0402-RES"))
    )
    (comp (ref "SJ401")
      (value "SOLDERJUMPERNO")
      (footprint "eagle-import:SJ_2S-NO")
      (libsource (lib "eagle-import") (part "SOLDERJUMPERNO"))
    )
    (comp (ref "SJ402")
      (value "SOLDERJUMPERNC2")
      (footprint "eagle-import:SJ_2S-NOTRACE")
      (libsource (lib "eagle-import") (part "SOLDERJUMPERNC2"))
    )
    (comp (ref "SJ403")
      (value "SOLDERJUMPERNC2")
      (footprint "eagle-import:SJ_2S-NOTRACE")
      (libsource (lib "eagle-import") (part "SOLDERJUMPERNC2"))
    )
    (comp (ref "U$401")
      (value "PESD0402-140")
      (footprint "eagle-import:0402-TVS")
      (libsource (lib "eagle-import") (part "DIODE-TVS"))
    )
    (comp (ref "U$402")
      (value "PESD0402-140")
      (footprint "eagle-import:0402-TVS")
      (libsource (lib "eagle-import") (part "DIODE-TVS"))
    )
    (comp (ref "U$403")
      (value "PESD0402-140")
      (footprint "eagle-import:0402-TVS")
      (libsource (lib "eagle-import") (part "DIODE-TVS"))
    )
    (comp (ref "U$404")
      (value "PESD0402-140")
      (footprint "eagle-import:0402-TVS")
      (libsource (lib "eagle-import") (part "DIODE-TVS"))
    )
    (comp (ref "U401")
      (value "MAX3051")
      (footprint "eagle-import:SOT23-8")
      (fields (field (name "PARTNO") "MAX3051EKA"))
      (libsource (lib "eagle-import") (part "MAX3051MAX3051EKA"))
    )
    (comp (ref "U402")
      (value "MAX3051")
      (footprint "eagle-import:SOT23-8")
      (fields (field (name "PARTNO") "MAX3051EKA"))
      (libsource (lib "eagle-import") (part "MAX3051MAX3051EKA"))
    )
    (comp (ref "C701")
      (value "2u2")
      (footprint "eagle-import:0603-CAP")
      (fields (field (name "PARTNO") "C1608Y5V1C225Z"))
      (libsource (lib "eagle-import") (part "CAP0603"))
    )
    (comp (ref "C702")
      (value "1u0")
      (footprint "eagle-import:0603-CAP")
      (fields (field (name "PARTNO") "CC0603ZRY5V7BB105"))
      (libsource (lib "eagle-import") (part "CAP0603"))
    )
    (comp (ref "C703")
      (value "10n")
      (footprint "eagle-import:0402-CAP")
      (fields (field (name "PARTNO") "CC0402KRX7R7BB103"))
      (libsource (lib "eagle-import") (part "CAP0402"))
    )
    (comp (ref "C704")
      (value "10n")
      (footprint "eagle-import:0402-CAP")
      (fields (field (name "PARTNO") "CC0402KRX7R7BB103"))
      (libsource (lib "eagle-import") (part "CAP0402"))
    )
    (comp (ref "C705")
      (value "1u0")
      (footprint "eagle-import:0603-CAP")
      (fields (field (name "PARTNO") "CC0603ZRY5V7BB105"))
      (libsource (lib "eagle-import") (part "CAP0603"))
    )
    (comp (ref "C706")
      (value "10u/10V")
      (footprint "eagle-import:0805-CAP")
      (fields (field (name "PARTNO") "CC0805ZKY5V6BB106"))
      (libsource (lib "eagle-import") (part "CAP0805"))
    )
    (comp (ref "C707")
      (value "1u0")
      (footprint "eagle-import:0603-CAP")
      (fields (field (name "PARTNO") "CC0603ZRY5V7BB105"))
      (libsource (lib "eagle-import") (part "CAP0603"))
    )
    (comp (ref "C708")
      (value "1u0")
      (footprint "eagle-import:0603-CAP")
      (fields (field (name "PARTNO") "CC0603ZRY5V7BB105"))
      (libsource (lib "eagle-import") (part "CAP0603"))
    )
    (comp (ref "C709")
      (value "1u0")
      (footprint "eagle-import:0603-CAP")
      (fields (field (name "PARTNO") "CC0603ZRY5V7BB105"))
      (libsource (lib "eagle-import") (part "CAP0603"))
    )
    (comp (ref "C710")
      (value "0u1")
      (footprint "eagle-import:0402-CAP")
      (fields (field (name "PARTNO") "CC0402ZRY5V7BB104"))
      (libsource (lib "eagle-import") (part "CAP0402"))
    )
    (comp (ref "C711")
      (value "0u1")
      (footprint "eagle-import:0402-CAP")
      (fields (field (name "PARTNO") "CC0402ZRY5V7BB104"))
      (libsource (lib "eagle-import") (part "CAP0402"))
    )
    (comp (ref "C712")
      (value "0u1")
      (footprint "eagle-import:0402-CAP")
      (fields (field (name "PARTNO") "CC0402ZRY5V7BB104"))
      (libsource (lib "eagle-import") (part "CAP0402"))
    )
    (comp (ref "C713")
      (value "0u1")
      (footprint "eagle-import:0402-CAP")
      (fields (field (name "PARTNO") "CC0402ZRY5V7BB104"))
      (libsource (lib "eagle-import") (part "CAP0402"))
    )
    (comp (ref "C714")
      (value "0u1")
      (footprint "eagle-import:0402-CAP")
      (fields (field (name "PARTNO") "CC0402ZRY5V7BB104"))
      (libsource (lib "eagle-import") (part "CAP0402"))
    )
    (comp (ref "C715")
      (value "0u1")
      (footprint "eagle-import:0402-CAP")
      (fields (field (name "PARTNO") "CC0402ZRY5V7BB104"))
      (libsource (lib "eagle-import") (part "CAP0402"))
    )
    (comp (ref "C716")
      (value "2u2")
      (footprint "eagle-import:0603-CAP")
      (fields (field (name "PARTNO") "C1608Y5V1C225Z"))
      (libsource (lib "eagle-import") (part "CAP0603"))
    )
    (comp (ref "C717")
      (value "0u1")
      (footprint "eagle-import:0402-CAP")
      (fields (field (name "PARTNO") "CC0402ZRY5V7BB104"))
      (libsource (lib "eagle-import") (part "CAP0402"))
    )
    (comp (ref "C718")
      (value "2u2")
      (footprint "eagle-import:0603-CAP")
      (fields (field (name "PARTNO") "C1608Y5V1C225Z"))
      (libsource (lib "eagle-import") (part "CAP0603"))
    )
    (comp (ref "D701")
      (value "MSS1P4-M3")
      (footprint "eagle-import:MICROSMP")
      (fields (field (name "PARTNO") "MSS1P4-M3/89A"))
      (libsource (lib "eagle-import") (part "DIODE-SCHOTTKY_MSMP"))
    )
    (comp (ref "JP701")
      (value "M01SMD-4.5X1.5")
      (footprint "eagle-import:PAD-1.5X4.5")
      (libsource (lib "eagle-import") (part "M01SMD-4.5X1.5"))
    )
    (comp (ref "JP702")
      (value "M01SMD-4.5X1.5")
      (footprint "eagle-import:PAD-1.5X4.5")
      (libsource (lib "eagle-import") (part "M01SMD-4.5X1.5"))
    )
    (comp (ref "R701")
      (value "10K")
      (footprint "eagle-import:0402-RES")
      (fields (field (name "PARTNO") "RC0402FR-0710KL"))
      (libsource (lib "eagle-import") (part "RESISTOR0402-RES"))
    )
    (comp (ref "R702")
      (value "10K")
      (footprint "eagle-import:0402-RES")
      (fields (field (name "PARTNO") "RC0402FR-0710KL"))
      (libsource (lib "eagle-import") (part "RESISTOR0402-RES"))
    )
    (comp (ref "R703")
      (value "10K")
      (footprint "eagle-import:0402-RES")
      (fields (field (name "PARTNO") "RC0402FR-0710KL"))
      (libsource (lib "eagle-import") (part "RESISTOR0402-RES"))
    )
    (comp (ref "R704")
      (value "47K")
      (footprint "eagle-import:0402-RES")
      (fields (field (name "PARTNO") "RMCF0402FT47K"))
      (libsource (lib "eagle-import") (part "RESISTOR0402-RES"))
    )
    (comp (ref "R705")
      (value "10K")
      (footprint "eagle-import:0402-RES")
      (fields (field (name "PARTNO") "RC0402FR-0710KL"))
      (libsource (lib "eagle-import") (part "RESISTOR0402-RES"))
    )
    (comp (ref "R706")
      (value "1K")
      (footprint "eagle-import:0402-RES")
      (fields (field (name "PARTNO") "RC0402FR-071KL"))
      (libsource (lib "eagle-import") (part "RESISTOR0402-RES"))
    )
    (comp (ref "R707")
      (value "10K/0.1%")
      (footprint "eagle-import:0402-RES")
      (fields (field (name "PARTNO") "ERA-2AEB103X"))
      (libsource (lib "eagle-import") (part "RESISTOR0402-RES"))
    )
    (comp (ref "R708")
      (value "10K/0.1%")
      (footprint "eagle-import:0402-RES")
      (fields (field (name "PARTNO") "ERA-2AEB103X"))
      (libsource (lib "eagle-import") (part "RESISTOR0402-RES"))
    )
    (comp (ref "R709")
      (value "10K")
      (footprint "eagle-import:0402-RES")
      (fields (field (name "PARTNO") "RC0402FR-0710KL"))
      (libsource (lib "eagle-import") (part "RESISTOR0402-RES"))
    )
    (comp (ref "S701")
      (value "RESET")
      (footprint "eagle-import:EVQP7J01K")
      (fields (field (name "PARTNO") "EVQP7J01K"))
      (libsource (lib "eagle-import") (part "SWITCH-MOMENTARY-2"))
    )
    (comp (ref "U$701")
      (value "MIC5332")
      (footprint "eagle-import:MLF-8-EPAD")
      (fields (field (name "PARTNO") "MIC5332-SSYMT"))
      (libsource (lib "eagle-import") (part "MIC5332"))
    )
    (comp (ref "U$702")
      (value "MIC5332")
      (footprint "eagle-import:MLF-8-EPAD")
      (fields (field (name "PARTNO") "MIC5332-SSYMT"))
      (libsource (lib "eagle-import") (part "MIC5332"))
    )
    (comp (ref "U$703")
      (value "BQ24315")
      (footprint "eagle-import:QFN8-DSG")
      (fields (field (name "PARTNO") "BQ24315DSGR"))
      (libsource (lib "eagle-import") (part "BQ24315"))
    )
    (comp (ref "BOOT")
      (value "PAD.04")
      (footprint "eagle-import:PAD.04X.04")
      (libsource (lib "eagle-import") (part "PAD.04"))
    )
    (comp (ref "JP1101")
      (value "FIDUCIAL1.5X3")
      (footprint "eagle-import:FIDUCIAL-1.5X3")
      (libsource (lib "eagle-import") (part "FIDUCIAL1.5X3"))
    )
    (comp (ref "JP1102")
      (value "FIDUCIAL1.5X3")
      (footprint "eagle-import:FIDUCIAL-1.5X3")
      (libsource (lib "eagle-import") (part "FIDUCIAL1.5X3"))
    )
    (comp (ref "JP1103")
      (value "FIDUCIAL1.5X3")
      (footprint "eagle-import:FIDUCIAL-1.5X3")
      (libsource (lib "eagle-import") (part "FIDUCIAL1.5X3"))
    )
    (comp (ref "JP1104")
      (value "FIDUCIAL1.5X3")
      (footprint "eagle-import:FIDUCIAL-1.5X3")
      (libsource (lib "eagle-import") (part "FIDUCIAL1.5X3"))
    )
    (comp (ref "M3_MOUNT1101")
      (value "MOUNT-HOLE3.1MM")
      (footprint "eagle-import:MOUNT-HOLE3.1")
      (libsource (lib "eagle-import") (part "MOUNT-HOLE3.1MM"))
    )
    (comp (ref "M3_MOUNT1102")
      (value "MOUNT-HOLE3.1MM")
      (footprint "eagle-import:MOUNT-HOLE3.1")
      (libsource (lib "eagle-import") (part "MOUNT-HOLE3.1MM"))
    )
    (comp (ref "M3_MOUNT1103")
      (value "MOUNT-HOLE3.1MM")
      (footprint "eagle-import:MOUNT-HOLE3.1")
      (libsource (lib "eagle-import") (part "MOUNT-HOLE3.1MM"))
    )
    (comp (ref "M3_MOUNT1104")
      (value "MOUNT-HOLE3.1MM")
      (footprint "eagle-import:MOUNT-HOLE3.1")
      (libsource (lib "eagle-import") (part "MOUNT-HOLE3.1MM"))
    )
    (comp (ref "OSHW_LOGO")
      (value "OSHW-LOGOS")
      (footprint "eagle-import:OSHW-LOGO-S")
      (libsource (lib "eagle-import") (part "OSHW-LOGOS"))
    )
    (comp (ref "C301")
      (value "2u2")
      (footprint "eagle-import:0603-CAP")
      (fields (field (name "PARTNO") "C1608Y5V1C225Z"))
      (libsource (lib "eagle-import") (part "CAP0603"))
    )
    (comp (ref "C302")
      (value "0u1")
      (footprint "eagle-import:0402-CAP")
      (fields (field (name "PARTNO") "CC0402ZRY5V7BB104"))
      (libsource (lib "eagle-import") (part "CAP0402"))
    )
    (comp (ref "J301")
      (value "DF13C-4P-1.25V")
      (footprint "eagle-import:DF13C-4P-1.25V")
      (fields (field (name "PARTNO") "DF13C-4P-1.25V(20)"))
      (libsource (lib "eagle-import") (part "DF13-4P-1.25V"))
    )
    (comp (ref "JX301")
      (value "ARM_MINI_JTAG-SMT")
      (footprint "eagle-import:FTSH-105-01-XXX-DV-K")
      (fields (field (name "BOM") "EXCLUDE") (field (name "PARTNO") "M50-3900542"))
      (libsource (lib "eagle-import") (part "ARM_MINI_JTAG-SMT"))
    )
    (comp (ref "U$301")
      (value "NUF2042XV6")
      (footprint "eagle-import:SOT563-6")
      (libsource (lib "eagle-import") (part "NUF2042XV6"))
    )
    (comp (ref "U$302")
      (value "W25Q64FV")
      (footprint "eagle-import:WSON-8-5X6")
      (libsource (lib "eagle-import") (part "W25Q64FV"))
    )
    (comp (ref "D901")
      (value "DIODESOD")
      (footprint "eagle-import:SOD-323")
      (libsource (lib "eagle-import") (part "DIODESOD"))
    )
    (comp (ref "D902")
      (value "B340A")
      (footprint "eagle-import:SMA-DIODE")
      (libsource (lib "eagle-import") (part "DIODESMA"))
    )
    (comp (ref "D903")
      (value "B340A")
      (footprint "eagle-import:SMA-DIODE")
      (libsource (lib "eagle-import") (part "DIODESMA"))
    )
    (comp (ref "D904")
      (value "MSS1P4-M3")
      (footprint "eagle-import:MICROSMP")
      (fields (field (name "PARTNO") "MSS1P4-M3/89A"))
      (libsource (lib "eagle-import") (part "DIODE-SCHOTTKY_MSMP"))
    )
    (comp (ref "JP901")
      (value "M02PTH3")
      (footprint "eagle-import:1X02_LONGPADS")
      (libsource (lib "eagle-import") (part "M02PTH3"))
    )
    (comp (ref "R901")
      (value "10K/0.1%")
      (footprint "eagle-import:0402-RES")
      (fields (field (name "PARTNO") "ERA-2AEB103X"))
      (libsource (lib "eagle-import") (part "RESISTOR0402-RES"))
    )
    (comp (ref "R902")
      (value "10K/0.1%")
      (footprint "eagle-import:0402-RES")
      (fields (field (name "PARTNO") "ERA-2AEB103X"))
      (libsource (lib "eagle-import") (part "RESISTOR0402-RES"))
    )
    (comp (ref "R903")
      (value "10K/0.1%")
      (footprint "eagle-import:0402-RES")
      (fields (field (name "PARTNO") "ERA-2AEB103X"))
      (libsource (lib "eagle-import") (part "RESISTOR0402-RES"))
    )
    (comp (ref "C601")
      (value "22uF")
      (footprint "eagle-import:1210")
      (libsource (lib "eagle-import") (part "22UF-16V-20%-(1210)"))
    )
    (comp (ref "C602")
      (value "0u1")
      (footprint "eagle-import:0402-CAP")
      (fields (field (name "PARTNO") "CC0402ZRY5V7BB104"))
      (libsource (lib "eagle-import") (part "CAP0402"))
    )
    (comp (ref "C603")
      (value "0u1")
      (footprint "eagle-import:0402-CAP")
      (fields (field (name "PARTNO") "CC0402ZRY5V7BB104"))
      (libsource (lib "eagle-import") (part "CAP0402"))
    )
    (comp (ref "C604")
      (value "0u1")
      (footprint "eagle-import:0402-CAP")
      (fields (field (name "PARTNO") "CC0402ZRY5V7BB104"))
      (libsource (lib "eagle-import") (part "CAP0402"))
    )
    (comp (ref "C605")
      (value "22uF")
      (footprint "eagle-import:1210")
      (libsource (lib "eagle-import") (part "22UF-16V-20%-(1210)"))
    )
    (comp (ref "C606")
      (value "22uF")
      (footprint "eagle-import:1210")
      (libsource (lib "eagle-import") (part "22UF-16V-20%-(1210)"))
    )
    (comp (ref "C607")
      (value "22uF")
      (footprint "eagle-import:1210")
      (libsource (lib "eagle-import") (part "22UF-16V-20%-(1210)"))
    )
    (comp (ref "L$601")
      (value "XFL4020-222MEB")
      (footprint "eagle-import:XFL4020")
      (libsource (lib "eagle-import") (part "XFL4020-222MEB"))
    )
    (comp (ref "U$601")
      (value "TPS6303X")
      (footprint "eagle-import:PWSON10")
      (libsource (lib "eagle-import") (part "TPS6303X"))
    )
    (comp (ref "J1001")
      (value "SERVO_HEADER-3X8")
      (footprint "eagle-import:3X8RA_SERVO")
      (fields (field (name "BOM") "EXCLUDE"))
      (libsource (lib "eagle-import") (part "SERVO_HEADER-3X8"))
    )
    (comp (ref "JP1001")
      (value "M01SMD-4.5X1.5")
      (footprint "eagle-import:PAD-1.5X4.5")
      (libsource (lib "eagle-import") (part "M01SMD-4.5X1.5"))
    )
    (comp (ref "JP1002")
      (value "M01SMD-4.5X1.5")
      (footprint "eagle-import:PAD-1.5X4.5")
      (libsource (lib "eagle-import") (part "M01SMD-4.5X1.5"))
    )
    (comp (ref "L1001")
      (value "NUF8402MN")
      (footprint "eagle-import:DFN16-THIN")
      (libsource (lib "eagle-import") (part "NUF8402MN"))
    )
    (comp (ref "R1001")
      (value "220R")
      (footprint "eagle-import:0402-RES")
      (fields (field (name "PARTNO") "RC0402FR-07220RL"))
      (libsource (lib "eagle-import") (part "RESISTOR0402-RES"))
    )
    (comp (ref "R1002")
      (value "220R")
      (footprint "eagle-import:0402-RES")
      (fields (field (name "PARTNO") "RC0402FR-07220RL"))
      (libsource (lib "eagle-import") (part "RESISTOR0402-RES"))
    )
    (comp (ref "J801")
      (value "DF13C-3P-1.25V")
      (footprint "eagle-import:DF13C-3P-1.25V")
      (fields (field (name "PARTNO") "DF13C-3P-1.25V(20)"))
      (libsource (lib "eagle-import") (part "DF13-3P-1.25V"))
    )
    (comp (ref "LED801")
      (value "AMBER")
      (footprint "eagle-import:0603-LED")
      (fields (field (name "PARTNO") "APTD1608SECK"))
      (libsource (lib "eagle-import") (part "LED0603"))
    )
    (comp (ref "LED802")
      (value "GREEN")
      (footprint "eagle-import:0603-LED")
      (fields (field (name "PARTNO") "APTD1608CGCK"))
      (libsource (lib "eagle-import") (part "LED0603"))
    )
    (comp (ref "R801")
      (value "47R")
      (footprint "eagle-import:0402-RES")
      (fields (field (name "PARTNO") "RC0402JR-0747RL"))
      (libsource (lib "eagle-import") (part "RESISTOR0402-RES"))
    )
    (comp (ref "R802")
      (value "1K5")
      (footprint "eagle-import:0402-RES")
      (fields (field (name "PARTNO") "RC0402FR-071K5L"))
      (libsource (lib "eagle-import") (part "RESISTOR0402-RES"))
    )
    (comp (ref "R803")
      (value "220R")
      (footprint "eagle-import:0402-RES")
      (fields (field (name "PARTNO") "RC0402FR-07220RL"))
      (libsource (lib "eagle-import") (part "RESISTOR0402-RES"))
    )
    (comp (ref "R804")
      (value "220R")
      (footprint "eagle-import:0402-RES")
      (fields (field (name "PARTNO") "RC0402FR-07220RL"))
      (libsource (lib "eagle-import") (part "RESISTOR0402-RES"))
    )
    (comp (ref "R805")
      (value "220R")
      (footprint "eagle-import:0402-RES")
      (fields (field (name "PARTNO") "RC0402FR-07220RL"))
      (libsource (lib "eagle-import") (part "RESISTOR0402-RES"))
    )
    (comp (ref "U$801")
      (value "PESD0402-140")
      (footprint "eagle-import:0402-TVS")
      (libsource (lib "eagle-import") (part "DIODE-TVS"))
    )
  )
  (nets
    (net (code "1") (name "5V_CAN_CONN") (class "Default")
      (node (ref "L405") (pin "P$1") (pinfunction "P$1_P$1") (pintype "bidirectional"))
      (node (ref "L406") (pin "P$1") (pinfunction "P$1_P$1") (pintype "bidirectional"))
      (node (ref "SJ401") (pin "2") (pinfunction "2_2") (pintype "passive"))
    )
    (net (code "2") (name "ACCEL_DRDY") (class "Default")
      (node (ref "U$501") (pin "11") (pinfunction "INT1_11") (pintype "bidirectional"))
      (node (ref "U101") (pin "90") (pinfunction "PB4_90") (pintype "bidirectional"))
    )
    (net (code "3") (name "ALARM") (class "Default")
      (node (ref "U101") (pin "77") (pinfunction "PA15_77") (pintype "bidirectional"))
    )
    (net (code "4") (name "CAN1_H") (class "Default")
      (node (ref "J405") (pin "P$2") (pinfunction "2_P$2") (pintype "passive"))
      (node (ref "R408") (pin "P$1") (pinfunction "1_P$1") (pintype "passive"))
      (node (ref "U402") (pin "7") (pinfunction "CANH_7") (pintype "bidirectional"))
    )
    (net (code "5") (name "CAN1_L") (class "Default")
      (node (ref "J405") (pin "P$3") (pinfunction "3_P$3") (pintype "passive"))
      (node (ref "SJ403") (pin "2") (pinfunction "2_2") (pintype "passive"))
      (node (ref "U402") (pin "6") (pinfunction "CANL_6") (pintype "bidirectional"))
    )
    (net (code "6") (name "CAN1_RX") (class "Default")
      (node (ref "U101") (pin "81") (pinfunction "PD0_81") (pintype "bidirectional"))
      (node (ref "U402") (pin "4") (pinfunction "DOUT_4") (pintype "output"))
    )
    (net (code "7") (name "CAN1_TX") (class "Default")
      (node (ref "U101") (pin "82") (pinfunction "PD1_82") (pintype "bidirectional"))
      (node (ref "U402") (pin "1") (pinfunction "DIN_1") (pintype "input"))
    )
    (net (code "8") (name "CAN2_RX") (class "Default")
      (node (ref "U101") (pin "51") (pinfunction "PB12_51") (pintype "bidirectional"))
      (node (ref "U401") (pin "4") (pinfunction "DOUT_4") (pintype "output"))
    )
    (net (code "9") (name "CAN2_TX") (class "Default")
      (node (ref "U101") (pin "92") (pinfunction "PB6_92") (pintype "bidirectional"))
      (node (ref "U401") (pin "1") (pinfunction "DIN_1") (pintype "input"))
    )
    (net (code "10") (name "FMU-BOOT0") (class "Default")
      (node (ref "BOOT") (pin "P$1") (pinfunction "P$1_P$1") (pintype "passive"))
      (node (ref "R709") (pin "P$2") (pinfunction "2_P$2") (pintype "passive"))
      (node (ref "U101") (pin "94") (pinfunction "BOOT0_94") (pintype "input"))
    )
    (net (code "11") (name "FMU-CH1") (class "Default")
      (node (ref "L1001") (pin "P$1") (pinfunction "P$1_P$1") (pintype "bidirectional"))
      (node (ref "U101") (pin "45") (pinfunction "PE14_45") (pintype "bidirectional"))
    )
    (net (code "12") (name "FMU-CH2") (class "Default")
      (node (ref "L1001") (pin "P$2") (pinfunction "P$1_P$2") (pintype "bidirectional"))
      (node (ref "U101") (pin "44") (pinfunction "PE13_44") (pintype "bidirectional"))
    )
    (net (code "13") (name "FMU-CH3") (class "Default")
      (node (ref "L1001") (pin "P$3") (pinfunction "P$1_P$3") (pintype "bidirectional"))
      (node (ref "U101") (pin "42") (pinfunction "PE11_42") (pintype "bidirectional"))
    )
    (net (code "14") (name "FMU-CH4") (class "Default")
      (node (ref "L1001") (pin "P$4") (pinfunction "P$1_P$4") (pintype "bidirectional"))
      (node (ref "U101") (pin "40") (pinfunction "PE9_40") (pintype "bidirectional"))
    )
    (net (code "15") (name "FMU-CH5") (class "Default")
      (node (ref "L1001") (pin "P$5") (pinfunction "P$1_P$5") (pintype "bidirectional"))
      (node (ref "U101") (pin "60") (pinfunction "PD13_60") (pintype "bidirectional"))
    )
    (net (code "16") (name "FMU-CH6") (class "Default")
      (node (ref "L1001") (pin "P$6") (pinfunction "P$1_P$6") (pintype "bidirectional"))
      (node (ref "U101") (pin "62") (pinfunction "PD15_62") (pintype "bidirectional"))
    )
    (net (code "17") (name "FMU-CH7") (class "Default")
      (node (ref "L1001") (pin "P$7") (pinfunction "P$1_P$7") (pintype "bidirectional"))
      (node (ref "U101") (pin "24") (pinfunction "PA1_24") (pintype "bidirectional"))
    )
    (net (code "18") (name "FMU-CH8") (class "Default")
      (node (ref "JP202") (pin "2") (pinfunction "2_2") (pintype "passive"))
      (node (ref "L1001") (pin "P$8") (pinfunction "P$1_P$8") (pintype "bidirectional"))
      (node (ref "U101") (pin "61") (pinfunction "PD14_61") (pintype "bidirectional"))
    )
    (net (code "19") (name "FMU-CH9") (class "Default")
      (node (ref "R1001") (pin "P$2") (pinfunction "2_P$2") (pintype "passive"))
      (node (ref "U101") (pin "25") (pinfunction "PA2_25") (pintype "bidirectional"))
    )
    (net (code "20") (name "FMU-CH10") (class "Default")
      (node (ref "R1002") (pin "P$2") (pinfunction "2_P$2") (pintype "passive"))
      (node (ref "U101") (pin "26") (pinfunction "PA3_26") (pintype "bidirectional"))
    )
    (net (code "21") (name "FMU-I2C1_SCL") (class "Default")
      (node (ref "L402") (pin "P$8") (pinfunction "P$1_P$8") (pintype "bidirectional"))
      (node (ref "R402") (pin "P$1") (pinfunction "1_P$1") (pintype "passive"))
      (node (ref "U101") (pin "95") (pinfunction "PB8_95") (pintype "bidirectional"))
    )
    (net (code "22") (name "FMU-I2C1_SDA") (class "Default")
      (node (ref "L402") (pin "P$7") (pinfunction "P$1_P$7") (pintype "bidirectional"))
      (node (ref "R404") (pin "P$1") (pinfunction "1_P$1") (pintype "passive"))
      (node (ref "U101") (pin "96") (pinfunction "PB9_96") (pintype "bidirectional"))
    )
    (net (code "23") (name "FMU-I2C2_SCL") (class "Default")
      (node (ref "L402") (pin "P$2") (pinfunction "P$1_P$2") (pintype "bidirectional"))
      (node (ref "R401") (pin "P$1") (pinfunction "1_P$1") (pintype "passive"))
      (node (ref "U101") (pin "47") (pinfunction "PB10_47") (pintype "bidirectional"))
    )
    (net (code "24") (name "FMU-I2C2_SDA") (class "Default")
      (node (ref "L402") (pin "P$1") (pinfunction "P$1_P$1") (pintype "bidirectional"))
      (node (ref "R403") (pin "P$1") (pinfunction "1_P$1") (pintype "passive"))
      (node (ref "U101") (pin "48") (pinfunction "PB11_48") (pintype "bidirectional"))
    )
    (net (code "25") (name "FMU-LED_SAFETY") (class "Default")
      (node (ref "R801") (pin "P$2") (pinfunction "2_P$2") (pintype "passive"))
    )
    (net (code "26") (name "FMU-SWCLK") (class "Default")
      (node (ref "JX301") (pin "4") (pinfunction "S_4") (pintype "passive"))
      (node (ref "U101") (pin "76") (pinfunction "PA14_76") (pintype "bidirectional"))
    )
    (net (code "27") (name "FMU-SWDIO") (class "Default")
      (node (ref "JX301") (pin "2") (pinfunction "S_2") (pintype "passive"))
      (node (ref "U101") (pin "72") (pinfunction "PA13_72") (pintype "bidirectional"))
    )
    (net (code "28") (name "FMU-SWO") (class "Default")
      (node (ref "JX301") (pin "6") (pinfunction "S_6") (pintype "passive"))
      (node (ref "U101") (pin "89") (pinfunction "PB3_89") (pintype "bidirectional"))
    )
    (net (code "29") (name "FMU-UART7_RX") (class "Default")
      (node (ref "L202") (pin "P$5") (pinfunction "P$1_P$5") (pintype "bidirectional"))
      (node (ref "U101") (pin "38") (pinfunction "PE7_38") (pintype "bidirectional"))
    )
    (net (code "30") (name "FMU-UART7_TX") (class "Default")
      (node (ref "L202") (pin "P$7") (pinfunction "P$1_P$7") (pintype "bidirectional"))
      (node (ref "U101") (pin "39") (pinfunction "PE8_39") (pintype "bidirectional"))
    )
    (net (code "31") (name "FMU-UART8_RX") (class "Default")
      (node (ref "U$202") (pin "6") (pinfunction "1Y_6") (pintype "bidirectional"))
      (node (ref "U101") (pin "97") (pinfunction "PE0_97") (pintype "bidirectional"))
    )
    (net (code "32") (name "FMU-UART8_TX") (class "Default")
      (node (ref "U$202") (pin "3") (pinfunction "2A_3") (pintype "bidirectional"))
      (node (ref "U101") (pin "98") (pinfunction "PE1_98") (pintype "bidirectional"))
    )
    (net (code "33") (name "FMU-USART2_CTS") (class "Default")
      (node (ref "L201") (pin "P$8") (pinfunction "P$1_P$8") (pintype "bidirectional"))
      (node (ref "U101") (pin "84") (pinfunction "PD3_84") (pintype "bidirectional"))
    )
    (net (code "34") (name "FMU-USART2_RTS") (class "Default")
      (node (ref "L201") (pin "P$7") (pinfunction "P$1_P$7") (pintype "bidirectional"))
      (node (ref "U101") (pin "85") (pinfunction "PD4_85") (pintype "bidirectional"))
    )
    (net (code "35") (name "FMU-USART2_RX") (class "Default")
      (node (ref "L201") (pin "P$5") (pinfunction "P$1_P$5") (pintype "bidirectional"))
      (node (ref "U101") (pin "87") (pinfunction "PD6_87") (pintype "bidirectional"))
    )
    (net (code "36") (name "FMU-USART2_TX") (class "Default")
      (node (ref "L201") (pin "P$6") (pinfunction "P$1_P$6") (pintype "bidirectional"))
      (node (ref "U101") (pin "86") (pinfunction "PD5_86") (pintype "bidirectional"))
    )
    (net (code "37") (name "FMU-USART3_CTS") (class "Default")
      (node (ref "L201") (pin "P$2") (pinfunction "P$1_P$2") (pintype "bidirectional"))
      (node (ref "U101") (pin "58") (pinfunction "PD11_58") (pintype "bidirectional"))
    )
    (net (code "38") (name "FMU-USART3_RTS") (class "Default")
      (node (ref "L201") (pin "P$1") (pinfunction "P$1_P$1") (pintype "bidirectional"))
      (node (ref "U101") (pin "59") (pinfunction "PD12_59") (pintype "bidirectional"))
    )
    (net (code "39") (name "FMU-USART3_RX") (class "Default")
      (node (ref "L201") (pin "P$3") (pinfunction "P$1_P$3") (pintype "bidirectional"))
      (node (ref "U101") (pin "56") (pinfunction "PD9_56") (pintype "bidirectional"))
    )
    (net (code "40") (name "FMU-USART3_TX") (class "Default")
      (node (ref "L201") (pin "P$4") (pinfunction "P$1_P$4") (pintype "bidirectional"))
      (node (ref "U101") (pin "55") (pinfunction "PD8_55") (pintype "bidirectional"))
    )
    (net (code "41") (name "FMU-VDD_3V3") (class "Default")
      (node (ref "C201") (pin "P$1") (pinfunction "1_P$1") (pintype "passive"))
      (node (ref "C301") (pin "P$1") (pinfunction "1_P$1") (pintype "passive"))
      (node (ref "C302") (pin "P$1") (pinfunction "1_P$1") (pintype "passive"))
      (node (ref "C401") (pin "P$1") (pinfunction "1_P$1") (pintype "passive"))
      (node (ref "C402") (pin "P$1") (pinfunction "1_P$1") (pintype "passive"))
      (node (ref "C705") (pin "P$1") (pinfunction "1_P$1") (pintype "passive"))
      (node (ref "C706") (pin "P$1") (pinfunction "1_P$1") (pintype "passive"))
      (node (ref "C710") (pin "P$1") (pinfunction "1_P$1") (pintype "passive"))
      (node (ref "C711") (pin "P$1") (pinfunction "1_P$1") (pintype "passive"))
      (node (ref "C712") (pin "P$1") (pinfunction "1_P$1") (pintype "passive"))
      (node (ref "C713") (pin "P$1") (pinfunction "1_P$1") (pintype "passive"))
      (node (ref "C715") (pin "P$1") (pinfunction "1_P$1") (pintype "passive"))
      (node (ref "C717") (pin "P$1") (pinfunction "1_P$1") (pintype "passive"))
      (node (ref "D701") (pin "ANODE") (pinfunction "A_ANODE") (pintype "passive"))
      (node (ref "J801") (pin "P$1") (pinfunction "1_P$1") (pintype "passive"))
      (node (ref "JX301") (pin "1") (pinfunction "S_1") (pintype "passive"))
      (node (ref "R401") (pin "P$2") (pinfunction "2_P$2") (pintype "passive"))
      (node (ref "R402") (pin "P$2") (pinfunction "2_P$2") (pintype "passive"))
      (node (ref "R403") (pin "P$2") (pinfunction "2_P$2") (pintype "passive"))
      (node (ref "R404") (pin "P$2") (pinfunction "2_P$2") (pintype "passive"))
      (node (ref "R702") (pin "P$1") (pinfunction "1_P$1") (pintype "passive"))
      (node (ref "U$202") (pin "5") (pinfunction "VCC_5") (pintype "power_in"))
      (node (ref "U$302") (pin "8") (pinfunction "VCC_8") (pintype "bidirectional"))
      (node (ref "U$701") (pin "7") (pinfunction "VOUT2_7") (pintype "bidirectional"))
      (node (ref "U$801") (pin "C") (pinfunction "C_C") (pintype "passive"))
      (node (ref "U101") (pin "100") (pinfunction "VDD_100") (pintype "power_in"))
      (node (ref "U101") (pin "11") (pinfunction "VDD_11") (pintype "power_in"))
      (node (ref "U101") (pin "19") (pinfunction "VDD_19") (pintype "power_in"))
      (node (ref "U101") (pin "21") (pinfunction "VREF+_21") (pintype "input"))
      (node (ref "U101") (pin "22") (pinfunction "VDDA_22") (pintype "power_in"))
      (node (ref "U101") (pin "28") (pinfunction "VDD_28") (pintype "power_in"))
      (node (ref "U101") (pin "50") (pinfunction "VDD_50") (pintype "power_in"))
      (node (ref "U101") (pin "75") (pinfunction "VDD_75") (pintype "power_in"))
      (node (ref "U401") (pin "3") (pinfunction "VCC_3") (pintype "input"))
      (node (ref "U402") (pin "3") (pinfunction "VCC_3") (pintype "input"))
    )
    (net (code "42") (name "FMU-~{RESET}") (class "Default")
      (node (ref "C714") (pin "P$2") (pinfunction "2_P$2") (pintype "passive"))
      (node (ref "JX301") (pin "10") (pinfunction "S_10") (pintype "passive"))
      (node (ref "S701") (pin "A1") (pinfunction "1_A1") (pintype "passive"))
      (node (ref "U$701") (pin "3") (pinfunction "POR2_3") (pintype "bidirectional"))
      (node (ref "U101") (pin "14") (pinfunction "NRST_14") (pintype "input"))
    )
    (net (code "43") (name "FMU_AUX_ADC1") (class "Default")
      (node (ref "R405") (pin "P$1") (pinfunction "1_P$1") (pintype "passive"))
      (node (ref "U101") (pin "18") (pinfunction "PC3_18") (pintype "bidirectional"))
    )
    (net (code "44") (name "FMU_AUX_ADC2") (class "Default")
      (node (ref "R406") (pin "P$1") (pinfunction "1_P$1") (pintype "passive"))
      (node (ref "U101") (pin "33") (pinfunction "PC4_33") (pintype "bidirectional"))
    )
    (net (code "45") (name "FRAM_MISO") (class "Default")
      (node (ref "U101") (pin "53") (pinfunction "PB14_53") (pintype "bidirectional"))
    )
    (net (code "46") (name "FRAM_MOSI") (class "Default")
      (node (ref "U101") (pin "54") (pinfunction "PB15_54") (pintype "bidirectional"))
    )
    (net (code "47") (name "FRAM_SCK") (class "Default")
      (node (ref "U101") (pin "52") (pinfunction "PB13_52") (pintype "bidirectional"))
    )
    (net (code "48") (name "GND") (class "Default")
      (node (ref "C101") (pin "P$2") (pinfunction "2_P$2") (pintype "passive"))
      (node (ref "C102") (pin "P$1") (pinfunction "1_P$1") (pintype "passive"))
      (node (ref "C201") (pin "P$2") (pinfunction "2_P$2") (pintype "passive"))
      (node (ref "C301") (pin "P$2") (pinfunction "2_P$2") (pintype "passive"))
      (node (ref "C302") (pin "P$2") (pinfunction "2_P$2") (pintype "passive"))
      (node (ref "C401") (pin "P$2") (pinfunction "2_P$2") (pintype "passive"))
      (node (ref "C402") (pin "P$2") (pinfunction "2_P$2") (pintype "passive"))
      (node (ref "C403") (pin "P$2") (pinfunction "2_P$2") (pintype "passive"))
      (node (ref "C404") (pin "P$2") (pinfunction "2_P$2") (pintype "passive"))
      (node (ref "C501") (pin "P$2") (pinfunction "2_P$2") (pintype "passive"))
      (node (ref "C502") (pin "P$2") (pinfunction "2_P$2") (pintype "passive"))
      (node (ref "C503") (pin "P$2") (pinfunction "2_P$2") (pintype "passive"))
      (node (ref "C601") (pin "2") (pinfunction "2_2") (pintype "passive"))
      (node (ref "C602") (pin "P$2") (pinfunction "2_P$2") (pintype "passive"))
      (node (ref "C603") (pin "P$2") (pinfunction "2_P$2") (pintype "passive"))
      (node (ref "C604") (pin "P$2") (pinfunction "2_P$2") (pintype "passive"))
      (node (ref "C605") (pin "2") (pinfunction "2_2") (pintype "passive"))
      (node (ref "C606") (pin "2") (pinfunction "2_2") (pintype "passive"))
      (node (ref "C607") (pin "2") (pinfunction "2_2") (pintype "passive"))
      (node (ref "C701") (pin "P$2") (pinfunction "2_P$2") (pintype "passive"))
      (node (ref "C702") (pin "P$2") (pinfunction "2_P$2") (pintype "passive"))
      (node (ref "C703") (pin "P$1") (pinfunction "1_P$1") (pintype "passive"))
      (node (ref "C704") (pin "P$2") (pinfunction "2_P$2") (pintype "passive"))
      (node (ref "C705") (pin "P$2") (pinfunction "2_P$2") (pintype "passive"))
      (node (ref "C706") (pin "P$2") (pinfunction "2_P$2") (pintype "passive"))
      (node (ref "C707") (pin "P$2") (pinfunction "2_P$2") (pintype "passive"))
      (node (ref "C708") (pin "P$2") (pinfunction "2_P$2") (pintype "passive"))
      (node (ref "C709") (pin "P$2") (pinfunction "2_P$2") (pintype "passive"))
      (node (ref "C710") (pin "P$2") (pinfunction "2_P$2") (pintype "passive"))
      (node (ref "C711") (pin "P$2") (pinfunction "2_P$2") (pintype "passive"))
      (node (ref "C712") (pin "P$2") (pinfunction "2_P$2") (pintype "passive"))
      (node (ref "C713") (pin "P$2") (pinfunction "2_P$2") (pintype "passive"))
      (node (ref "C714") (pin "P$1") (pinfunction "1_P$1") (pintype "passive"))
      (node (ref "C715") (pin "P$2") (pinfunction "2_P$2") (pintype "passive"))
      (node (ref "C716") (pin "P$2") (pinfunction "2_P$2") (pintype "passive"))
      (node (ref "C717") (pin "P$2") (pinfunction "2_P$2") (pintype "passive"))
      (node (ref "C718") (pin "P$2") (pinfunction "2_P$2") (pintype "passive"))
      (node (ref "D901") (pin "2") (pinfunction "A_2") (pintype "passive"))
      (node (ref "J$401") (pin "3") (pinfunction "3_3") (pintype "bidirectional"))
      (node (ref "J1001") (pin "GND_S1") (pinfunction "S_GND_S1") (pintype "passive"))
      (node (ref "J1001") (pin "GND_S2") (pinfunction "S_GND_S2") (pintype "passive"))
      (node (ref "J1001") (pin "GND_S3") (pinfunction "S_GND_S3") (pintype "passive"))
      (node (ref "J1001") (pin "GND_S4") (pinfunction "S_GND_S4") (pintype "passive"))
      (node (ref "J1001") (pin "GND_S5") (pinfunction "S_GND_S5") (pintype "passive"))
      (node (ref "J1001") (pin "GND_S6") (pinfunction "S_GND_S6") (pintype "passive"))
      (node (ref "J1001") (pin "GND_S7") (pinfunction "S_GND_S7") (pintype "passive"))
      (node (ref "J1001") (pin "GND_S8") (pinfunction "S_GND_S8") (pintype "passive"))
      (node (ref "J201") (pin "P$6") (pinfunction "6_P$6") (pintype "passive"))
      (node (ref "J202") (pin "P$6") (pinfunction "6_P$6") (pintype "passive"))
      (node (ref "J203") (pin "P$6") (pinfunction "6_P$6") (pintype "passive"))
      (node (ref "J301") (pin "P$4") (pinfunction "4_P$4") (pintype "passive"))
      (node (ref "J401") (pin "P$7") (pinfunction "7_P$7") (pintype "passive"))
      (node (ref "J402") (pin "P$4") (pinfunction "4_P$4") (pintype "passive"))
      (node (ref "J403") (pin "P$4") (pinfunction "4_P$4") (pintype "passive"))
      (node (ref "J404") (pin "P$4") (pinfunction "4_P$4") (pintype "passive"))
      (node (ref "J405") (pin "P$4") (pinfunction "4_P$4") (pintype "passive"))
      (node (ref "JP702") (pin "P$1") (pinfunction "1_P$1") (pintype "passive"))
      (node (ref "JP901") (pin "2") (pinfunction "2_2") (pintype "passive"))
      (node (ref "JX301") (pin "3") (pinfunction "S_3") (pintype "passive"))
      (node (ref "JX301") (pin "5") (pinfunction "S_5") (pintype "passive"))
      (node (ref "JX301") (pin "9") (pinfunction "S_9") (pintype "passive"))
      (node (ref "L1001") (pin "P$EP") (pinfunction "GND_P$EP") (pintype "power_in"))
      (node (ref "L201") (pin "P$EP") (pinfunction "GND_P$EP") (pintype "power_in"))
      (node (ref "L202") (pin "P$1") (pinfunction "P$1_P$1") (pintype "bidirectional"))
      (node (ref "L202") (pin "P$15") (pinfunction "P$2_P$15") (pintype "bidirectional"))
      (node (ref "L202") (pin "P$16") (pinfunction "P$2_P$16") (pintype "bidirectional"))
      (node (ref "L202") (pin "P$2") (pinfunction "P$1_P$2") (pintype "bidirectional"))
      (node (ref "L202") (pin "P$EP") (pinfunction "GND_P$EP") (pintype "power_in"))
      (node (ref "L203") (pin "P$3") (pinfunction "P$3_P$3") (pintype "bidirectional"))
      (node (ref "L203") (pin "P$4") (pinfunction "P$3_P$4") (pintype "bidirectional"))
      (node (ref "L203") (pin "P$5") (pinfunction "P$3_P$5") (pintype "bidirectional"))
      (node (ref "L204") (pin "P$3") (pinfunction "P$3_P$3") (pintype "bidirectional"))
      (node (ref "L204") (pin "P$4") (pinfunction "P$3_P$4") (pintype "bidirectional"))
      (node (ref "L204") (pin "P$5") (pinfunction "P$3_P$5") (pintype "bidirectional"))
      (node (ref "L205") (pin "P$3") (pinfunction "P$3_P$3") (pintype "bidirectional"))
      (node (ref "L205") (pin "P$4") (pinfunction "P$3_P$4") (pintype "bidirectional"))
      (node (ref "L205") (pin "P$5") (pinfunction "P$3_P$5") (pintype "bidirectional"))
      (node (ref "L401") (pin "P$3") (pinfunction "P$3_P$3") (pintype "bidirectional"))
      (node (ref "L401") (pin "P$4") (pinfunction "P$3_P$4") (pintype "bidirectional"))
      (node (ref "L401") (pin "P$5") (pinfunction "P$3_P$5") (pintype "bidirectional"))
      (node (ref "L402") (pin "P$EP") (pinfunction "GND_P$EP") (pintype "power_in"))
      (node (ref "L403") (pin "P$3") (pinfunction "P$3_P$3") (pintype "bidirectional"))
      (node (ref "L403") (pin "P$4") (pinfunction "P$3_P$4") (pintype "bidirectional"))
      (node (ref "L403") (pin "P$5") (pinfunction "P$3_P$5") (pintype "bidirectional"))
      (node (ref "L404") (pin "P$3") (pinfunction "P$3_P$3") (pintype "bidirectional"))
      (node (ref "L404") (pin "P$4") (pinfunction "P$3_P$4") (pintype "bidirectional"))
      (node (ref "L404") (pin "P$5") (pinfunction "P$3_P$5") (pintype "bidirectional"))
      (node (ref "L405") (pin "P$3") (pinfunction "P$3_P$3") (pintype "bidirectional"))
      (node (ref "L405") (pin "P$4") (pinfunction "P$3_P$4") (pintype "bidirectional"))
      (node (ref "L405") (pin "P$5") (pinfunction "P$3_P$5") (pintype "bidirectional"))
      (node (ref "L406") (pin "P$3") (pinfunction "P$3_P$3") (pintype "bidirectional"))
      (node (ref "L406") (pin "P$4") (pinfunction "P$3_P$4") (pintype "bidirectional"))
      (node (ref "L406") (pin "P$5") (pinfunction "P$3_P$5") (pintype "bidirectional"))
      (node (ref "R101") (pin "P$2") (pinfunction "2_P$2") (pintype "passive"))
      (node (ref "R701") (pin "P$1") (pinfunction "1_P$1") (pintype "passive"))
      (node (ref "R703") (pin "P$1") (pinfunction "1_P$1") (pintype "passive"))
      (node (ref "R704") (pin "P$2") (pinfunction "2_P$2") (pintype "passive"))
      (node (ref "R708") (pin "P$2") (pinfunction "2_P$2") (pintype "passive"))
      (node (ref "R709") (pin "P$1") (pinfunction "1_P$1") (pintype "passive"))
      (node (ref "R802") (pin "P$2") (pinfunction "2_P$2") (pintype "passive"))
      (node (ref "R805") (pin "P$1") (pinfunction "1_P$1") (pintype "passive"))
      (node (ref "R903") (pin "P$1") (pinfunction "1_P$1") (pintype "passive"))
      (node (ref "S701") (pin "B3") (pinfunction "2_B3") (pintype "passive"))
      (node (ref "U$201") (pin "3") (pinfunction "3_3") (pintype "bidirectional"))
      (node (ref "U$202") (pin "2") (pinfunction "GND_2") (pintype "power_in"))
      (node (ref "U$203") (pin "A") (pinfunction "A_A") (pintype "passive"))
      (node (ref "U$204") (pin "A") (pinfunction "A_A") (pintype "passive"))
      (node (ref "U$205") (pin "A") (pinfunction "A_A") (pintype "passive"))
      (node (ref "U$301") (pin "2") (pinfunction "GND_2") (pintype "bidirectional"))
      (node (ref "U$302") (pin "4") (pinfunction "GND_4") (pintype "bidirectional"))
      (node (ref "U$302") (pin "PAD") (pinfunction "GND_PAD") (pintype "bidirectional"))
      (node (ref "U$401") (pin "A") (pinfunction "A_A") (pintype "passive"))
      (node (ref "U$402") (pin "A") (pinfunction "A_A") (pintype "passive"))
      (node (ref "U$403") (pin "A") (pinfunction "A_A") (pintype "passive"))
      (node (ref "U$404") (pin "A") (pinfunction "A_A") (pintype "passive"))
      (node (ref "U$501") (pin "10") (pinfunction "RSV1_10") (pintype "input"))
      (node (ref "U$501") (pin "5") (pinfunction "GND_5") (pintype "power_in"))
      (node (ref "U$601") (pin "11") (pinfunction "GND_11") (pintype "power_in"))
      (node (ref "U$601") (pin "15") (pinfunction "PGND_15") (pintype "power_in"))
      (node (ref "U$601") (pin "16") (pinfunction "PGND_16") (pintype "power_in"))
      (node (ref "U$601") (pin "17") (pinfunction "PGND_17") (pintype "power_in"))
      (node (ref "U$601") (pin "18") (pinfunction "PGND_18") (pintype "power_in"))
      (node (ref "U$601") (pin "19") (pinfunction "PGND_19") (pintype "power_in"))
      (node (ref "U$601") (pin "20") (pinfunction "PGND_20") (pintype "power_in"))
      (node (ref "U$601") (pin "21") (pinfunction "PGND_21") (pintype "power_in"))
      (node (ref "U$601") (pin "22") (pinfunction "PGND_22") (pintype "power_in"))
      (node (ref "U$601") (pin "23") (pinfunction "PGND_23") (pintype "power_in"))
      (node (ref "U$601") (pin "4") (pinfunction "PS/SYNC_4") (pintype "input"))
      (node (ref "U$601") (pin "6") (pinfunction "PGND_6") (pintype "power_in"))
      (node (ref "U$601") (pin "7") (pinfunction "PGND_7") (pintype "power_in"))
      (node (ref "U$601") (pin "8") (pinfunction "PGND_8") (pintype "power_in"))
      (node (ref "U$601") (pin "9") (pinfunction "PGND_9") (pintype "power_in"))
      (node (ref "U$601") (pin "EP") (pinfunction "PGND_EP") (pintype "power_in"))
      (node (ref "U$601") (pin "EP1") (pinfunction "PGND_EP1") (pintype "power_in"))
      (node (ref "U$701") (pin "2") (pinfunction "GND_2") (pintype "bidirectional"))
      (node (ref "U$701") (pin "GND") (pinfunction "GND_GND") (pintype "bidirectional"))
      (node (ref "U$702") (pin "2") (pinfunction "GND_2") (pintype "bidirectional"))
      (node (ref "U$702") (pin "GND") (pinfunction "GND_GND") (pintype "bidirectional"))
      (node (ref "U$703") (pin "2") (pinfunction "VSS_2") (pintype "bidirectional"))
      (node (ref "U$703") (pin "6") (pinfunction "VBAT_6") (pintype "bidirectional"))
      (node (ref "U$703") (pin "GND") (pinfunction "VSS_GND") (pintype "bidirectional"))
      (node (ref "U$703") (pin "P$2") (pinfunction "VSS_P$2") (pintype "bidirectional"))
      (node (ref "U$703") (pin "P$3") (pinfunction "VSS_P$3") (pintype "bidirectional"))
      (node (ref "U$801") (pin "A") (pinfunction "A_A") (pintype "passive"))
      (node (ref "U101") (pin "10") (pinfunction "VSS_10") (pintype "power_in"))
      (node (ref "U101") (pin "20") (pinfunction "VSSA_20") (pintype "power_in"))
      (node (ref "U101") (pin "27") (pinfunction "VSS_27") (pintype "power_in"))
      (node (ref "U101") (pin "74") (pinfunction "VSS_74") (pintype "power_in"))
      (node (ref "U101") (pin "99") (pinfunction "VSS_99") (pintype "power_in"))
      (node (ref "U401") (pin "2") (pinfunction "GND_2") (pintype "power_in"))
      (node (ref "U401") (pin "5") (pinfunction "SHDN_5") (pintype "input"))
      (node (ref "U401") (pin "8") (pinfunction "RS_8") (pintype "input"))
      (node (ref "U402") (pin "2") (pinfunction "GND_2") (pintype "power_in"))
      (node (ref "U402") (pin "5") (pinfunction "SHDN_5") (pintype "input"))
      (node (ref "U402") (pin "8") (pinfunction "RS_8") (pintype "input"))
      (node (ref "X101") (pin "2") (pinfunction "NC_2_2") (pintype "power_in"))
      (node (ref "X101") (pin "4") (pinfunction "NC_4_4") (pintype "power_in"))
    )
    (net (code "49") (name "GPIO_EXT_1") (class "Default")
      (node (ref "J401") (pin "P$6") (pinfunction "6_P$6") (pintype "passive"))
      (node (ref "U101") (pin "8") (pinfunction "PC14_8") (pintype "bidirectional"))
    )
    (net (code "50") (name "GYRO_DRDY") (class "Default")
      (node (ref "U$501") (pin "9") (pinfunction "INT2_9") (pintype "bidirectional"))
      (node (ref "U101") (pin "35") (pinfunction "PB0_35") (pintype "bidirectional"))
    )
    (net (code "51") (name "IO-~{RESET}") (class "Default")
      (node (ref "U$702") (pin "3") (pinfunction "POR2_3") (pintype "bidirectional"))
    )
    (net (code "52") (name "MAG_DRDY") (class "Default")
      (node (ref "U$501") (pin "12") (pinfunction "DSYNC_12") (pintype "bidirectional"))
      (node (ref "U101") (pin "36") (pinfunction "PB1_36") (pintype "bidirectional"))
    )
    (net (code "53") (name "Net-(C101-1)") (class "Default")
      (node (ref "C101") (pin "P$1") (pinfunction "1_P$1") (pintype "passive"))
      (node (ref "U101") (pin "12") (pinfunction "OSC_IN_12") (pintype "input"))
      (node (ref "X101") (pin "3") (pinfunction "3_3") (pintype "bidirectional"))
    )
    (net (code "54") (name "Net-(C102-2)") (class "Default")
      (node (ref "C102") (pin "P$2") (pinfunction "2_P$2") (pintype "passive"))
      (node (ref "U101") (pin "13") (pinfunction "OSC_OUT_13") (pintype "output"))
      (node (ref "X101") (pin "1") (pinfunction "1_1") (pintype "bidirectional"))
    )
    (net (code "55") (name "Net-(C403-1)") (class "Default")
      (node (ref "C403") (pin "P$1") (pinfunction "1_P$1") (pintype "passive"))
      (node (ref "J$401") (pin "2") (pinfunction "2_2") (pintype "bidirectional"))
      (node (ref "R405") (pin "P$2") (pinfunction "2_P$2") (pintype "passive"))
    )
    (net (code "56") (name "Net-(C404-1)") (class "Default")
      (node (ref "C404") (pin "P$1") (pinfunction "1_P$1") (pintype "passive"))
      (node (ref "J$401") (pin "1") (pinfunction "1_1") (pintype "bidirectional"))
      (node (ref "R406") (pin "P$2") (pinfunction "2_P$2") (pintype "passive"))
    )
    (net (code "57") (name "Net-(C503-1)") (class "Default")
      (node (ref "C503") (pin "P$1") (pinfunction "1_P$1") (pintype "passive"))
      (node (ref "U$501") (pin "13") (pinfunction "REGD_13") (pintype "power_in"))
    )
    (net (code "58") (name "Net-(C603-1)") (class "Default")
      (node (ref "C603") (pin "P$1") (pinfunction "1_P$1") (pintype "passive"))
      (node (ref "U$601") (pin "10") (pinfunction "VAUX_10") (pintype "input"))
    )
    (net (code "59") (name "Net-(C703-2)") (class "Default")
      (node (ref "C703") (pin "P$2") (pinfunction "2_P$2") (pintype "passive"))
      (node (ref "U$701") (pin "6") (pinfunction "CSET_6") (pintype "bidirectional"))
    )
    (net (code "60") (name "Net-(C704-1)") (class "Default")
      (node (ref "C704") (pin "P$1") (pinfunction "1_P$1") (pintype "passive"))
      (node (ref "U$702") (pin "6") (pinfunction "CSET_6") (pintype "bidirectional"))
    )
    (net (code "61") (name "Net-(C716-1)") (class "Default")
      (node (ref "C716") (pin "P$1") (pinfunction "1_P$1") (pintype "passive"))
      (node (ref "U101") (pin "49") (pinfunction "VCAP_1_49") (pintype "power_in"))
    )
    (net (code "62") (name "Net-(C718-1)") (class "Default")
      (node (ref "C718") (pin "P$1") (pinfunction "1_P$1") (pintype "passive"))
      (node (ref "U101") (pin "73") (pinfunction "VCAP_2_73") (pintype "power_in"))
    )
    (net (code "63") (name "Net-(D701-C)") (class "Default")
      (node (ref "D701") (pin "CATHODE") (pinfunction "C_CATHODE") (pintype "passive"))
      (node (ref "R706") (pin "P$2") (pinfunction "2_P$2") (pintype "passive"))
    )
    (net (code "64") (name "Net-(D901-C)") (class "Default")
      (node (ref "D901") (pin "1") (pinfunction "C_1") (pintype "passive"))
      (node (ref "R901") (pin "P$1") (pinfunction "1_P$1") (pintype "passive"))
      (node (ref "R902") (pin "P$2") (pinfunction "2_P$2") (pintype "passive"))
    )
    (net (code "65") (name "Net-(J201-1)") (class "Default")
      (node (ref "J201") (pin "P$1") (pinfunction "1_P$1") (pintype "passive"))
      (node (ref "L203") (pin "P$2") (pinfunction "P$2_P$2") (pintype "bidirectional"))
      (node (ref "U$203") (pin "C") (pinfunction "C_C") (pintype "passive"))
    )
    (net (code "66") (name "Net-(J202-1)") (class "Default")
      (node (ref "J202") (pin "P$1") (pinfunction "1_P$1") (pintype "passive"))
      (node (ref "L204") (pin "P$2") (pinfunction "P$2_P$2") (pintype "bidirectional"))
      (node (ref "U$204") (pin "C") (pinfunction "C_C") (pintype "passive"))
    )
    (net (code "67") (name "Net-(J203-1)") (class "Default")
      (node (ref "J203") (pin "P$1") (pinfunction "1_P$1") (pintype "passive"))
      (node (ref "L205") (pin "P$2") (pinfunction "P$2_P$2") (pintype "bidirectional"))
      (node (ref "U$205") (pin "C") (pinfunction "C_C") (pintype "passive"))
    )
    (net (code "68") (name "Net-(J301-2)") (class "Default")
      (node (ref "J301") (pin "P$2") (pinfunction "2_P$2") (pintype "passive"))
      (node (ref "U$301") (pin "1") (pinfunction "D1I_1") (pintype "bidirectional"))
    )
    (net (code "69") (name "Net-(J301-3)") (class "Default")
      (node (ref "J301") (pin "P$3") (pinfunction "3_P$3") (pintype "passive"))
      (node (ref "U$301") (pin "3") (pinfunction "D2I_3") (pintype "bidirectional"))
    )
    (net (code "70") (name "Net-(J401-1)") (class "Default")
      (node (ref "J401") (pin "P$1") (pinfunction "1_P$1") (pintype "passive"))
      (node (ref "L401") (pin "P$2") (pinfunction "P$2_P$2") (pintype "bidirectional"))
    )
    (net (code "71") (name "Net-(J402-1)") (class "Default")
      (node (ref "J402") (pin "P$1") (pinfunction "1_P$1") (pintype "passive"))
      (node (ref "L403") (pin "P$2") (pinfunction "P$2_P$2") (pintype "bidirectional"))
      (node (ref "U$401") (pin "C") (pinfunction "C_C") (pintype "passive"))
    )
    (net (code "72") (name "Net-(J402-2)") (class "Default")
      (node (ref "J402") (pin "P$2") (pinfunction "2_P$2") (pintype "passive"))
      (node (ref "L402") (pin "P$15") (pinfunction "P$2_P$15") (pintype "bidirectional"))
    )
    (net (code "73") (name "Net-(J402-3)") (class "Default")
      (node (ref "J402") (pin "P$3") (pinfunction "3_P$3") (pintype "passive"))
      (node (ref "L402") (pin "P$16") (pinfunction "P$2_P$16") (pintype "bidirectional"))
    )
    (net (code "74") (name "Net-(J403-1)") (class "Default")
      (node (ref "J403") (pin "P$1") (pinfunction "1_P$1") (pintype "passive"))
      (node (ref "L404") (pin "P$2") (pinfunction "P$2_P$2") (pintype "bidirectional"))
      (node (ref "U$402") (pin "C") (pinfunction "C_C") (pintype "passive"))
    )
    (net (code "75") (name "Net-(J403-2)") (class "Default")
      (node (ref "J403") (pin "P$2") (pinfunction "2_P$2") (pintype "passive"))
      (node (ref "L402") (pin "P$9") (pinfunction "P$2_P$9") (pintype "bidirectional"))
    )
    (net (code "76") (name "Net-(J403-3)") (class "Default")
      (node (ref "J403") (pin "P$3") (pinfunction "3_P$3") (pintype "passive"))
      (node (ref "L402") (pin "P$10") (pinfunction "P$2_P$10") (pintype "bidirectional"))
    )
    (net (code "77") (name "Net-(J404-1)") (class "Default")
      (node (ref "J404") (pin "P$1") (pinfunction "1_P$1") (pintype "passive"))
      (node (ref "L405") (pin "P$2") (pinfunction "P$2_P$2") (pintype "bidirectional"))
      (node (ref "U$403") (pin "C") (pinfunction "C_C") (pintype "passive"))
    )
    (net (code "78") (name "Net-(J404-2)") (class "Default")
      (node (ref "J404") (pin "P$2") (pinfunction "2_P$2") (pintype "passive"))
      (node (ref "R407") (pin "P$1") (pinfunction "1_P$1") (pintype "passive"))
      (node (ref "U401") (pin "7") (pinfunction "CANH_7") (pintype "bidirectional"))
    )
    (net (code "79") (name "Net-(J404-3)") (class "Default")
      (node (ref "J404") (pin "P$3") (pinfunction "3_P$3") (pintype "passive"))
      (node (ref "SJ402") (pin "2") (pinfunction "2_2") (pintype "passive"))
      (node (ref "U401") (pin "6") (pinfunction "CANL_6") (pintype "bidirectional"))
    )
    (net (code "80") (name "Net-(J405-1)") (class "Default")
      (node (ref "J405") (pin "P$1") (pinfunction "1_P$1") (pintype "passive"))
      (node (ref "L406") (pin "P$2") (pinfunction "P$2_P$2") (pintype "bidirectional"))
      (node (ref "U$404") (pin "C") (pinfunction "C_C") (pintype "passive"))
    )
    (net (code "81") (name "Net-(J801-2)") (class "Default")
      (node (ref "J801") (pin "P$2") (pinfunction "2_P$2") (pintype "passive"))
      (node (ref "R801") (pin "P$1") (pinfunction "1_P$1") (pintype "passive"))
    )
    (net (code "82") (name "Net-(J1001A-S)") (class "Default")
      (node (ref "J1001") (pin "S1") (pinfunction "S_S1") (pintype "passive"))
      (node (ref "L1001") (pin "P$16") (pinfunction "P$2_P$16") (pintype "bidirectional"))
    )
    (net (code "83") (name "Net-(J1001B-S)") (class "Default")
      (node (ref "J1001") (pin "S2") (pinfunction "S_S2") (pintype "passive"))
      (node (ref "L1001") (pin "P$15") (pinfunction "P$2_P$15") (pintype "bidirectional"))
    )
    (net (code "84") (name "Net-(J1001C-S)") (class "Default")
      (node (ref "J1001") (pin "S3") (pinfunction "S_S3") (pintype "passive"))
      (node (ref "L1001") (pin "P$14") (pinfunction "P$2_P$14") (pintype "bidirectional"))
    )
    (net (code "85") (name "Net-(J1001D-S)") (class "Default")
      (node (ref "J1001") (pin "S4") (pinfunction "S_S4") (pintype "passive"))
      (node (ref "L1001") (pin "P$13") (pinfunction "P$2_P$13") (pintype "bidirectional"))
    )
    (net (code "86") (name "Net-(J1001E-S)") (class "Default")
      (node (ref "J1001") (pin "S5") (pinfunction "S_S5") (pintype "passive"))
      (node (ref "L1001") (pin "P$12") (pinfunction "P$2_P$12") (pintype "bidirectional"))
    )
    (net (code "87") (name "Net-(J1001F-S)") (class "Default")
      (node (ref "J1001") (pin "S6") (pinfunction "S_S6") (pintype "passive"))
      (node (ref "L1001") (pin "P$11") (pinfunction "P$2_P$11") (pintype "bidirectional"))
    )
    (net (code "88") (name "Net-(J1001G-S)") (class "Default")
      (node (ref "J1001") (pin "S7") (pinfunction "S_S7") (pintype "passive"))
      (node (ref "L1001") (pin "P$10") (pinfunction "P$2_P$10") (pintype "bidirectional"))
    )
    (net (code "89") (name "Net-(J1001H-S)") (class "Default")
      (node (ref "J1001") (pin "S8") (pinfunction "S_S8") (pintype "passive"))
      (node (ref "L1001") (pin "P$9") (pinfunction "P$2_P$9") (pintype "bidirectional"))
    )
    (net (code "90") (name "Net-(JP201-Pad2)") (class "Default")
      (node (ref "JP201") (pin "2") (pinfunction "2_2") (pintype "passive"))
      (node (ref "U$201") (pin "2") (pinfunction "2_2") (pintype "bidirectional"))
    )
    (net (code "91") (name "Net-(JP1001-1)") (class "Default")
      (node (ref "JP1001") (pin "P$1") (pinfunction "1_P$1") (pintype "passive"))
      (node (ref "R1001") (pin "P$1") (pinfunction "1_P$1") (pintype "passive"))
    )
    (net (code "92") (name "Net-(JP1002-1)") (class "Default")
      (node (ref "JP1002") (pin "P$1") (pinfunction "1_P$1") (pintype "passive"))
      (node (ref "R1002") (pin "P$1") (pinfunction "1_P$1") (pintype "passive"))
    )
    (net (code "93") (name "Net-(L202C-P$2)") (class "Default")
      (node (ref "L202") (pin "P$13") (pinfunction "P$2_P$13") (pintype "bidirectional"))
      (node (ref "L202") (pin "P$14") (pinfunction "P$2_P$14") (pintype "bidirectional"))
      (node (ref "U$201") (pin "1") (pinfunction "1_1") (pintype "bidirectional"))
    )
    (net (code "94") (name "Net-(R101-1)") (class "Default")
      (node (ref "R101") (pin "P$1") (pinfunction "1_P$1") (pintype "passive"))
      (node (ref "U101") (pin "37") (pinfunction "PB2_37") (pintype "bidirectional"))
    )
    (net (code "95") (name "Net-(R407-2)") (class "Default")
      (node (ref "R407") (pin "P$2") (pinfunction "2_P$2") (pintype "passive"))
      (node (ref "SJ402") (pin "1") (pinfunction "1_1") (pintype "passive"))
    )
    (net (code "96") (name "Net-(R408-2)") (class "Default")
      (node (ref "R408") (pin "P$2") (pinfunction "2_P$2") (pintype "passive"))
      (node (ref "SJ403") (pin "1") (pinfunction "1_1") (pintype "passive"))
    )
    (net (code "97") (name "Net-(R704-1)") (class "Default")
      (node (ref "R704") (pin "P$1") (pinfunction "1_P$1") (pintype "passive"))
      (node (ref "U$703") (pin "7") (pinfunction "ILIM_7") (pintype "bidirectional"))
    )
    (net (code "98") (name "Net-(R803-1)") (class "Default")
      (node (ref "R803") (pin "P$1") (pinfunction "1_P$1") (pintype "passive"))
      (node (ref "R804") (pin "P$2") (pinfunction "2_P$2") (pintype "passive"))
    )
    (net (code "99") (name "Net-(R803-2)") (class "Default")
      (node (ref "LED801") (pin "C") (pinfunction "C_C") (pintype "passive"))
      (node (ref "R803") (pin "P$2") (pinfunction "2_P$2") (pintype "passive"))
    )
    (net (code "100") (name "Net-(R805-2)") (class "Default")
      (node (ref "LED802") (pin "C") (pinfunction "C_C") (pintype "passive"))
      (node (ref "R805") (pin "P$2") (pinfunction "2_P$2") (pintype "passive"))
    )
    (net (code "101") (name "Net-(U$202-2Y)") (class "Default")
      (node (ref "JP202") (pin "1") (pinfunction "1_1") (pintype "passive"))
      (node (ref "U$202") (pin "4") (pinfunction "2Y_4") (pintype "bidirectional"))
    )
    (net (code "102") (name "Net-(U$601-L1)") (class "Default")
      (node (ref "L$601") (pin "2") (pinfunction "2_2") (pintype "passive"))
      (node (ref "U$601") (pin "1") (pinfunction "L1_1") (pintype "bidirectional"))
    )
    (net (code "103") (name "Net-(U$601-L2)") (class "Default")
      (node (ref "L$601") (pin "1") (pinfunction "1_1") (pintype "passive"))
      (node (ref "U$601") (pin "14") (pinfunction "L2_14") (pintype "bidirectional"))
    )
    (net (code "104") (name "OTG_FS_DM") (class "Default")
      (node (ref "U$301") (pin "4") (pinfunction "D2O_4") (pintype "bidirectional"))
      (node (ref "U101") (pin "70") (pinfunction "PA11_70") (pintype "bidirectional"))
    )
    (net (code "105") (name "OTG_FS_DP") (class "Default")
      (node (ref "U$301") (pin "6") (pinfunction "D1O_6") (pintype "bidirectional"))
      (node (ref "U101") (pin "71") (pinfunction "PA12_71") (pintype "bidirectional"))
    )
    (net (code "106") (name "PPM_INPUT") (class "Default")
      (node (ref "L202") (pin "P$3") (pinfunction "P$1_P$3") (pintype "bidirectional"))
      (node (ref "U$202") (pin "1") (pinfunction "1A_1") (pintype "bidirectional"))
      (node (ref "U101") (pin "23") (pinfunction "PA0_23") (pintype "bidirectional"))
    )
    (net (code "107") (name "SAFETY") (class "Default")
      (node (ref "J801") (pin "P$3") (pinfunction "3_P$3") (pintype "passive"))
      (node (ref "R802") (pin "P$1") (pinfunction "1_P$1") (pintype "passive"))
    )
    (net (code "108") (name "SDIO_CK") (class "Default")
      (node (ref "U$302") (pin "6") (pinfunction "CLK_6") (pintype "bidirectional"))
      (node (ref "U101") (pin "80") (pinfunction "PC12_80") (pintype "bidirectional"))
    )
    (net (code "109") (name "SDIO_CMD") (class "Default")
      (node (ref "U$302") (pin "1") (pinfunction "~{CS}_1") (pintype "bidirectional"))
      (node (ref "U101") (pin "83") (pinfunction "PD2_83") (pintype "bidirectional"))
    )
    (net (code "110") (name "SDIO_D0") (class "Default")
      (node (ref "U$302") (pin "5") (pinfunction "DI/IO0_5") (pintype "bidirectional"))
      (node (ref "U101") (pin "65") (pinfunction "PC8_65") (pintype "bidirectional"))
    )
    (net (code "111") (name "SDIO_D1") (class "Default")
      (node (ref "U$302") (pin "2") (pinfunction "DO/IO1_2") (pintype "bidirectional"))
      (node (ref "U101") (pin "66") (pinfunction "PC9_66") (pintype "bidirectional"))
    )
    (net (code "112") (name "SDIO_D2") (class "Default")
      (node (ref "U$302") (pin "3") (pinfunction "~{WP}/IO2_3") (pintype "bidirectional"))
      (node (ref "U101") (pin "78") (pinfunction "PC10_78") (pintype "bidirectional"))
    )
    (net (code "113") (name "SDIO_D3") (class "Default")
      (node (ref "U$302") (pin "7") (pinfunction "~{HOLD}/IO3_7") (pintype "bidirectional"))
      (node (ref "U101") (pin "79") (pinfunction "PC11_79") (pintype "bidirectional"))
    )
    (net (code "114") (name "SERIAL1_CTS") (class "Default")
      (node (ref "J201") (pin "P$4") (pinfunction "4_P$4") (pintype "passive"))
      (node (ref "L201") (pin "P$9") (pinfunction "P$2_P$9") (pintype "bidirectional"))
    )
    (net (code "115") (name "SERIAL1_RTS") (class "Default")
      (node (ref "J201") (pin "P$5") (pinfunction "5_P$5") (pintype "passive"))
      (node (ref "L201") (pin "P$10") (pinfunction "P$2_P$10") (pintype "bidirectional"))
    )
    (net (code "116") (name "SERIAL1_RX") (class "Default")
      (node (ref "J201") (pin "P$3") (pinfunction "3_P$3") (pintype "passive"))
      (node (ref "L201") (pin "P$12") (pinfunction "P$2_P$12") (pintype "bidirectional"))
    )
    (net (code "117") (name "SERIAL1_TX") (class "Default")
      (node (ref "J201") (pin "P$2") (pinfunction "2_P$2") (pintype "passive"))
      (node (ref "L201") (pin "P$11") (pinfunction "P$2_P$11") (pintype "bidirectional"))
    )
    (net (code "118") (name "SERIAL2_CTS") (class "Default")
      (node (ref "J202") (pin "P$4") (pinfunction "4_P$4") (pintype "passive"))
      (node (ref "L201") (pin "P$15") (pinfunction "P$2_P$15") (pintype "bidirectional"))
    )
    (net (code "119") (name "SERIAL2_RTS") (class "Default")
      (node (ref "J202") (pin "P$5") (pinfunction "5_P$5") (pintype "passive"))
      (node (ref "L201") (pin "P$16") (pinfunction "P$2_P$16") (pintype "bidirectional"))
    )
    (net (code "120") (name "SERIAL2_RX") (class "Default")
      (node (ref "J202") (pin "P$3") (pinfunction "3_P$3") (pintype "passive"))
      (node (ref "L201") (pin "P$14") (pinfunction "P$2_P$14") (pintype "bidirectional"))
    )
    (net (code "121") (name "SERIAL2_TX") (class "Default")
      (node (ref "J202") (pin "P$2") (pinfunction "2_P$2") (pintype "passive"))
      (node (ref "L201") (pin "P$13") (pinfunction "P$2_P$13") (pintype "bidirectional"))
    )
    (net (code "122") (name "SERIAL3_RX") (class "Default")
      (node (ref "J203") (pin "P$3") (pinfunction "3_P$3") (pintype "passive"))
      (node (ref "L202") (pin "P$12") (pinfunction "P$2_P$12") (pintype "bidirectional"))
    )
    (net (code "123") (name "SERIAL3_TX") (class "Default")
      (node (ref "J203") (pin "P$2") (pinfunction "2_P$2") (pintype "passive"))
      (node (ref "L202") (pin "P$10") (pinfunction "P$2_P$10") (pintype "bidirectional"))
    )
    (net (code "124") (name "SPEKTRUM_RX") (class "Default")
      (node (ref "L202") (pin "P$4") (pinfunction "P$1_P$4") (pintype "bidirectional"))
      (node (ref "U101") (pin "69") (pinfunction "PA10_69") (pintype "bidirectional"))
    )
    (net (code "125") (name "SPI_EXT_MISO") (class "Default")
      (node (ref "J401") (pin "P$3") (pinfunction "3_P$3") (pintype "passive"))
      (node (ref "U101") (pin "4") (pinfunction "PE5_4") (pintype "bidirectional"))
    )
    (net (code "126") (name "SPI_EXT_MOSI") (class "Default")
      (node (ref "J401") (pin "P$4") (pinfunction "4_P$4") (pintype "passive"))
      (node (ref "U101") (pin "5") (pinfunction "PE6_5") (pintype "bidirectional"))
    )
    (net (code "127") (name "SPI_EXT_SCK") (class "Default")
      (node (ref "J401") (pin "P$2") (pinfunction "2_P$2") (pintype "passive"))
      (node (ref "U101") (pin "1") (pinfunction "PE2_1") (pintype "bidirectional"))
    )
    (net (code "128") (name "SPI_INT_MISO") (class "Default")
      (node (ref "U$501") (pin "7") (pinfunction "SA0/MISO_7") (pintype "bidirectional"))
      (node (ref "U101") (pin "31") (pinfunction "PA6_31") (pintype "bidirectional"))
    )
    (net (code "129") (name "SPI_INT_MOSI") (class "Default")
      (node (ref "U$501") (pin "6") (pinfunction "SDA/MOSI_6") (pintype "bidirectional"))
      (node (ref "U101") (pin "32") (pinfunction "PA7_32") (pintype "bidirectional"))
    )
    (net (code "130") (name "SPI_INT_SCK") (class "Default")
      (node (ref "U$501") (pin "4") (pinfunction "SCL/CLK_4") (pintype "bidirectional"))
      (node (ref "U101") (pin "30") (pinfunction "PA5_30") (pintype "bidirectional"))
    )
    (net (code "131") (name "VBAT") (class "Default")
      (node (ref "JP701") (pin "P$1") (pinfunction "1_P$1") (pintype "passive"))
      (node (ref "R706") (pin "P$1") (pinfunction "1_P$1") (pintype "passive"))
      (node (ref "U101") (pin "6") (pinfunction "VBAT_6") (pintype "power_in"))
    )
    (net (code "132") (name "VBUS") (class "Default")
      (node (ref "D904") (pin "ANODE") (pinfunction "A_ANODE") (pintype "passive"))
      (node (ref "J301") (pin "P$1") (pinfunction "1_P$1") (pintype "passive"))
      (node (ref "U$301") (pin "5") (pinfunction "VBUS_5") (pintype "bidirectional"))
      (node (ref "U101") (pin "68") (pinfunction "PA9_68") (pintype "bidirectional"))
    )
    (net (code "133") (name "VDD_3V3_PERIPH") (class "Default")
      (node (ref "C709") (pin "P$1") (pinfunction "1_P$1") (pintype "passive"))
      (node (ref "U$702") (pin "7") (pinfunction "VOUT2_7") (pintype "bidirectional"))
    )
    (net (code "134") (name "VDD_3V3_PERIPH_EN") (class "Default")
      (node (ref "R703") (pin "P$2") (pinfunction "2_P$2") (pintype "passive"))
      (node (ref "U$702") (pin "4") (pinfunction "EN2_4") (pintype "bidirectional"))
    )
    (net (code "135") (name "VDD_3V3_SENSORS") (class "Default")
      (node (ref "C501") (pin "P$1") (pinfunction "1_P$1") (pintype "passive"))
      (node (ref "C502") (pin "P$1") (pinfunction "1_P$1") (pintype "passive"))
      (node (ref "C707") (pin "P$1") (pinfunction "1_P$1") (pintype "passive"))
      (node (ref "U$501") (pin "1") (pinfunction "VDD_IO_1") (pintype "power_in"))
      (node (ref "U$501") (pin "14") (pinfunction "VDD_14") (pintype "power_in"))
      (node (ref "U$501") (pin "15") (pinfunction "RSV2_15") (pintype "input"))
      (node (ref "U$702") (pin "8") (pinfunction "VOUT1_8") (pintype "bidirectional"))
    )
    (net (code "136") (name "VDD_3V3_SENSORS_EN") (class "Default")
      (node (ref "R702") (pin "P$2") (pinfunction "2_P$2") (pintype "passive"))
      (node (ref "U$702") (pin "5") (pinfunction "EN1_5") (pintype "bidirectional"))
      (node (ref "U101") (pin "2") (pinfunction "PE3_2") (pintype "bidirectional"))
    )
    (net (code "137") (name "VDD_3V3_SPEKTRUM") (class "Default")
      (node (ref "C708") (pin "P$1") (pinfunction "1_P$1") (pintype "passive"))
      (node (ref "JP201") (pin "1") (pinfunction "1_1") (pintype "passive"))
      (node (ref "U$701") (pin "8") (pinfunction "VOUT1_8") (pintype "bidirectional"))
    )
    (net (code "138") (name "VDD_3V3_SPEKTRUM_EN") (class "Default")
      (node (ref "R701") (pin "P$2") (pinfunction "2_P$2") (pintype "passive"))
      (node (ref "U$701") (pin "5") (pinfunction "EN1_5") (pintype "bidirectional"))
      (node (ref "U101") (pin "17") (pinfunction "PC2_17") (pintype "bidirectional"))
    )
    (net (code "139") (name "VDD_5V") (class "Default")
      (node (ref "C604") (pin "P$1") (pinfunction "1_P$1") (pintype "passive"))
      (node (ref "C605") (pin "1") (pinfunction "1_1") (pintype "passive"))
      (node (ref "C606") (pin "1") (pinfunction "1_1") (pintype "passive"))
      (node (ref "C607") (pin "1") (pinfunction "1_1") (pintype "passive"))
      (node (ref "C701") (pin "P$1") (pinfunction "1_P$1") (pintype "passive"))
      (node (ref "C702") (pin "P$1") (pinfunction "1_P$1") (pintype "passive"))
      (node (ref "LED801") (pin "A") (pinfunction "A_A") (pintype "passive"))
      (node (ref "LED802") (pin "A") (pinfunction "A_A") (pintype "passive"))
      (node (ref "R705") (pin "P$1") (pinfunction "1_P$1") (pintype "passive"))
      (node (ref "R707") (pin "P$2") (pinfunction "2_P$2") (pintype "passive"))
      (node (ref "U$601") (pin "13") (pinfunction "VOUT_13") (pintype "power_in"))
      (node (ref "U$701") (pin "1") (pinfunction "VIN_1") (pintype "bidirectional"))
      (node (ref "U$701") (pin "4") (pinfunction "EN2_4") (pintype "bidirectional"))
      (node (ref "U$702") (pin "1") (pinfunction "VIN_1") (pintype "bidirectional"))
      (node (ref "U$703") (pin "1") (pinfunction "IN_1") (pintype "bidirectional"))
    )
    (net (code "140") (name "VDD_5V_PERIPH") (class "Default")
      (node (ref "JP201") (pin "3") (pinfunction "3_3") (pintype "passive"))
      (node (ref "L203") (pin "P$1") (pinfunction "P$1_P$1") (pintype "bidirectional"))
      (node (ref "L204") (pin "P$1") (pinfunction "P$1_P$1") (pintype "bidirectional"))
      (node (ref "L205") (pin "P$1") (pinfunction "P$1_P$1") (pintype "bidirectional"))
      (node (ref "L401") (pin "P$1") (pinfunction "P$1_P$1") (pintype "bidirectional"))
      (node (ref "L403") (pin "P$1") (pinfunction "P$1_P$1") (pintype "bidirectional"))
      (node (ref "L404") (pin "P$1") (pinfunction "P$1_P$1") (pintype "bidirectional"))
      (node (ref "SJ401") (pin "1") (pinfunction "1_1") (pintype "passive"))
      (node (ref "U$703") (pin "8") (pinfunction "OUT_8") (pintype "bidirectional"))
    )
    (net (code "141") (name "VDD_5V_SENS") (class "Default")
      (node (ref "R707") (pin "P$1") (pinfunction "1_P$1") (pintype "passive"))
      (node (ref "R708") (pin "P$1") (pinfunction "1_P$1") (pintype "passive"))
      (node (ref "U101") (pin "29") (pinfunction "PA4_29") (pintype "bidirectional"))
    )
    (net (code "142") (name "VDD_IN") (class "Default")
      (node (ref "C601") (pin "1") (pinfunction "1_1") (pintype "passive"))
      (node (ref "C602") (pin "P$1") (pinfunction "1_P$1") (pintype "passive"))
      (node (ref "D902") (pin "C") (pinfunction "C_C") (pintype "passive"))
      (node (ref "D903") (pin "C") (pinfunction "C_C") (pintype "passive"))
      (node (ref "D904") (pin "CATHODE") (pinfunction "C_CATHODE") (pintype "passive"))
      (node (ref "U$601") (pin "2") (pinfunction "VIN_2") (pintype "power_in"))
      (node (ref "U$601") (pin "3") (pinfunction "EN_3") (pintype "input"))
    )
    (net (code "143") (name "VDD_SERVO_SENS") (class "Default")
      (node (ref "R902") (pin "P$1") (pinfunction "1_P$1") (pintype "passive"))
      (node (ref "R903") (pin "P$2") (pinfunction "2_P$2") (pintype "passive"))
    )
    (net (code "144") (name "V_EXT") (class "Default")
      (node (ref "D903") (pin "A") (pinfunction "A_A") (pintype "passive"))
      (node (ref "JP901") (pin "1") (pinfunction "1_1") (pintype "passive"))
      (node (ref "R901") (pin "P$2") (pinfunction "2_P$2") (pintype "passive"))
    )
    (net (code "145") (name "V_SERVO") (class "Default")
      (node (ref "D902") (pin "A") (pinfunction "A_A") (pintype "passive"))
      (node (ref "J1001") (pin "PWR_S1") (pinfunction "S_PWR_S1") (pintype "passive"))
      (node (ref "J1001") (pin "PWR_S2") (pinfunction "S_PWR_S2") (pintype "passive"))
      (node (ref "J1001") (pin "PWR_S3") (pinfunction "S_PWR_S3") (pintype "passive"))
      (node (ref "J1001") (pin "PWR_S4") (pinfunction "S_PWR_S4") (pintype "passive"))
      (node (ref "J1001") (pin "PWR_S5") (pinfunction "S_PWR_S5") (pintype "passive"))
      (node (ref "J1001") (pin "PWR_S6") (pinfunction "S_PWR_S6") (pintype "passive"))
      (node (ref "J1001") (pin "PWR_S7") (pinfunction "S_PWR_S7") (pintype "passive"))
      (node (ref "J1001") (pin "PWR_S8") (pinfunction "S_PWR_S8") (pintype "passive"))
    )
    (net (code "146") (name "unconnected-(J203-4-PadP$4)") (class "Default")
      (node (ref "J203") (pin "P$4") (pinfunction "4_P$4") (pintype "passive"))
    )
    (net (code "147") (name "unconnected-(J203-5-PadP$5)") (class "Default")
      (node (ref "J203") (pin "P$5") (pinfunction "5_P$5") (pintype "passive"))
    )
    (net (code "148") (name "unconnected-(JX301F-S-Pad8)") (class "Default")
      (node (ref "JX301") (pin "8") (pinfunction "S_8") (pintype "passive"))
    )
    (net (code "149") (name "unconnected-(L202F-P$1-PadP$6)") (class "Default")
      (node (ref "L202") (pin "P$6") (pinfunction "P$1_P$6") (pintype "bidirectional"))
    )
    (net (code "150") (name "unconnected-(L202F-P$2-PadP$11)") (class "Default")
      (node (ref "L202") (pin "P$11") (pinfunction "P$2_P$11") (pintype "bidirectional"))
    )
    (net (code "151") (name "unconnected-(L202H-P$1-PadP$8)") (class "Default")
      (node (ref "L202") (pin "P$8") (pinfunction "P$1_P$8") (pintype "bidirectional"))
    )
    (net (code "152") (name "unconnected-(L202H-P$2-PadP$9)") (class "Default")
      (node (ref "L202") (pin "P$9") (pinfunction "P$2_P$9") (pintype "bidirectional"))
    )
    (net (code "153") (name "unconnected-(L402C-P$1-PadP$3)") (class "Default")
      (node (ref "L402") (pin "P$3") (pinfunction "P$1_P$3") (pintype "bidirectional"))
    )
    (net (code "154") (name "unconnected-(L402C-P$2-PadP$14)") (class "Default")
      (node (ref "L402") (pin "P$14") (pinfunction "P$2_P$14") (pintype "bidirectional"))
    )
    (net (code "155") (name "unconnected-(L402D-P$1-PadP$4)") (class "Default")
      (node (ref "L402") (pin "P$4") (pinfunction "P$1_P$4") (pintype "bidirectional"))
    )
    (net (code "156") (name "unconnected-(L402D-P$2-PadP$13)") (class "Default")
      (node (ref "L402") (pin "P$13") (pinfunction "P$2_P$13") (pintype "bidirectional"))
    )
    (net (code "157") (name "unconnected-(L402E-P$1-PadP$5)") (class "Default")
      (node (ref "L402") (pin "P$5") (pinfunction "P$1_P$5") (pintype "bidirectional"))
    )
    (net (code "158") (name "unconnected-(L402E-P$2-PadP$12)") (class "Default")
      (node (ref "L402") (pin "P$12") (pinfunction "P$2_P$12") (pintype "bidirectional"))
    )
    (net (code "159") (name "unconnected-(L402F-P$1-PadP$6)") (class "Default")
      (node (ref "L402") (pin "P$6") (pinfunction "P$1_P$6") (pintype "bidirectional"))
    )
    (net (code "160") (name "unconnected-(L402F-P$2-PadP$11)") (class "Default")
      (node (ref "L402") (pin "P$11") (pinfunction "P$2_P$11") (pintype "bidirectional"))
    )
    (net (code "161") (name "unconnected-(U$501-MST_SCL-Pad2)") (class "Default")
      (node (ref "U$501") (pin "2") (pinfunction "MST_SCL_2") (pintype "bidirectional"))
    )
    (net (code "162") (name "unconnected-(U$501-MST_SDA-Pad3)") (class "Default")
      (node (ref "U$501") (pin "3") (pinfunction "MST_SDA_3") (pintype "bidirectional"))
    )
    (net (code "163") (name "unconnected-(U$501-RSV3-Pad16)") (class "Default")
      (node (ref "U$501") (pin "16") (pinfunction "RSV3_16") (pintype "no_connect"))
    )
    (net (code "164") (name "unconnected-(U$601-FB-Pad12)") (class "Default")
      (node (ref "U$601") (pin "12") (pinfunction "FB_12") (pintype "input"))
    )
    (net (code "165") (name "unconnected-(U$601-PG-Pad5)") (class "Default")
      (node (ref "U$601") (pin "5") (pinfunction "PG_5") (pintype "output"))
    )
    (net (code "166") (name "unconnected-(U101I-PC0-Pad15)") (class "Default")
      (node (ref "U101") (pin "15") (pinfunction "PC0_15") (pintype "bidirectional"))
    )
    (net (code "167") (name "unconnected-(U101I-PC1-Pad16)") (class "Default")
      (node (ref "U101") (pin "16") (pinfunction "PC1_16") (pintype "bidirectional"))
    )
    (net (code "168") (name "unconnected-(U101I-PC5-Pad34)") (class "Default")
      (node (ref "U101") (pin "34") (pinfunction "PC5_34") (pintype "bidirectional"))
    )
    (net (code "169") (name "unconnected-(U101I-PC6-Pad63)") (class "Default")
      (node (ref "U101") (pin "63") (pinfunction "PC6_63") (pintype "bidirectional"))
    )
    (net (code "170") (name "unconnected-(U101I-PC7-Pad64)") (class "Default")
      (node (ref "U101") (pin "64") (pinfunction "PC7_64") (pintype "bidirectional"))
    )
    (net (code "171") (name "unconnected-(U101L-PE10-Pad41)") (class "Default")
      (node (ref "U101") (pin "41") (pinfunction "PE10_41") (pintype "bidirectional"))
    )
    (net (code "172") (name "~{ACCEL_MAG_CS}") (class "Default")
      (node (ref "U101") (pin "9") (pinfunction "PC15_9") (pintype "bidirectional"))
    )
    (net (code "173") (name "~{BARO_CS}") (class "Default")
      (node (ref "U101") (pin "88") (pinfunction "PD7_88") (pintype "bidirectional"))
    )
    (net (code "174") (name "~{EX_VDD_5V_VALID}") (class "Default")
      (node (ref "U101") (pin "91") (pinfunction "PB5_91") (pintype "bidirectional"))
    )
    (net (code "175") (name "~{FMU-LED_AMBER}") (class "Default")
      (node (ref "R804") (pin "P$1") (pinfunction "1_P$1") (pintype "passive"))
      (node (ref "U101") (pin "43") (pinfunction "PE12_43") (pintype "bidirectional"))
    )
    (net (code "176") (name "~{FRAM_CS}") (class "Default")
      (node (ref "U101") (pin "57") (pinfunction "PD10_57") (pintype "bidirectional"))
    )
    (net (code "177") (name "~{GYRO_CS}") (class "Default")
      (node (ref "U$501") (pin "8") (pinfunction "CS_8") (pintype "bidirectional"))
      (node (ref "U101") (pin "7") (pinfunction "PC13_7") (pintype "bidirectional"))
    )
    (net (code "178") (name "~{SPI_EXT_NSS}") (class "Default")
      (node (ref "J401") (pin "P$5") (pinfunction "5_P$5") (pintype "passive"))
      (node (ref "U101") (pin "3") (pinfunction "PE4_3") (pintype "bidirectional"))
    )
    (net (code "179") (name "~{VDD_5V_PERIPH_EN}") (class "Default")
      (node (ref "R705") (pin "P$2") (pinfunction "2_P$2") (pintype "passive"))
      (node (ref "U$703") (pin "5") (pinfunction "~{CE}_5") (pintype "bidirectional"))
      (node (ref "U101") (pin "67") (pinfunction "PA8_67") (pintype "bidirectional"))
    )
    (net (code "180") (name "~{VDD_5V_PERIPH_OC}") (class "Default")
      (node (ref "U$703") (pin "4") (pinfunction "~{FAULT}_4") (pintype "bidirectional"))
      (node (ref "U101") (pin "46") (pinfunction "PE15_46") (pintype "bidirectional"))
    )
    (net (code "181") (name "~{VDD_SERVO_VALID}") (class "Default")
      (node (ref "U101") (pin "93") (pinfunction "PB7_93") (pintype "bidirectional"))
    )
  )
)
